# SzineszFeny_V11.net
KiCad netlist of a schematic drawn in EAGLE
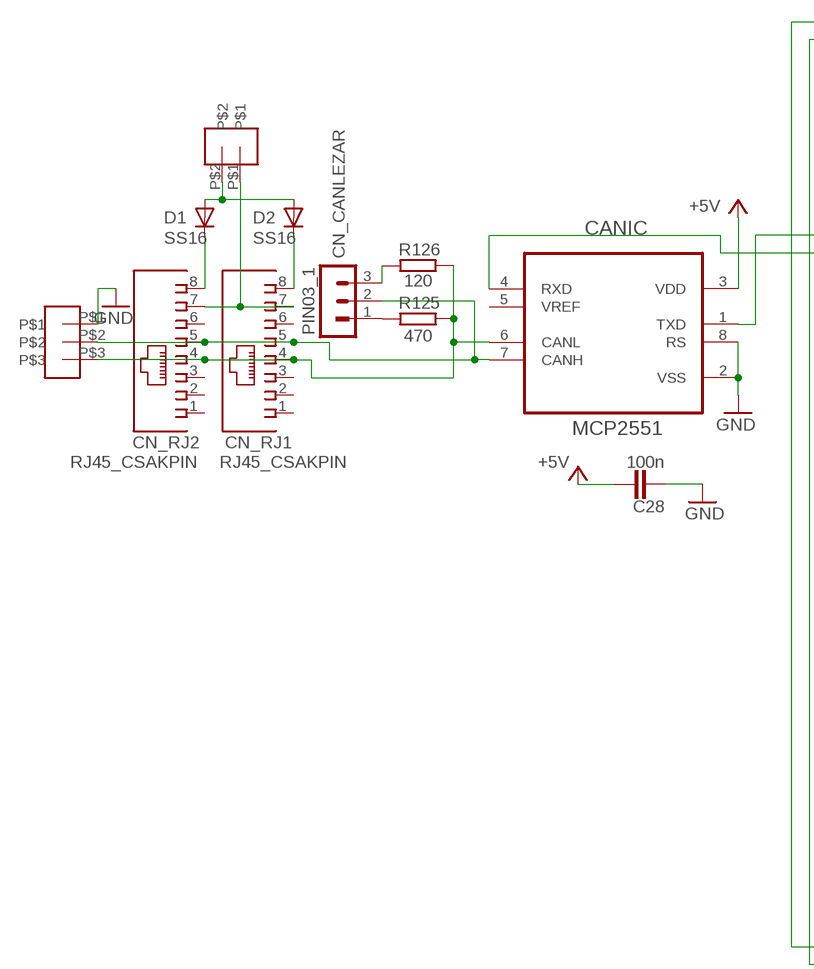
[diagram p0: schematic, sheet 1, part 1 of 2]
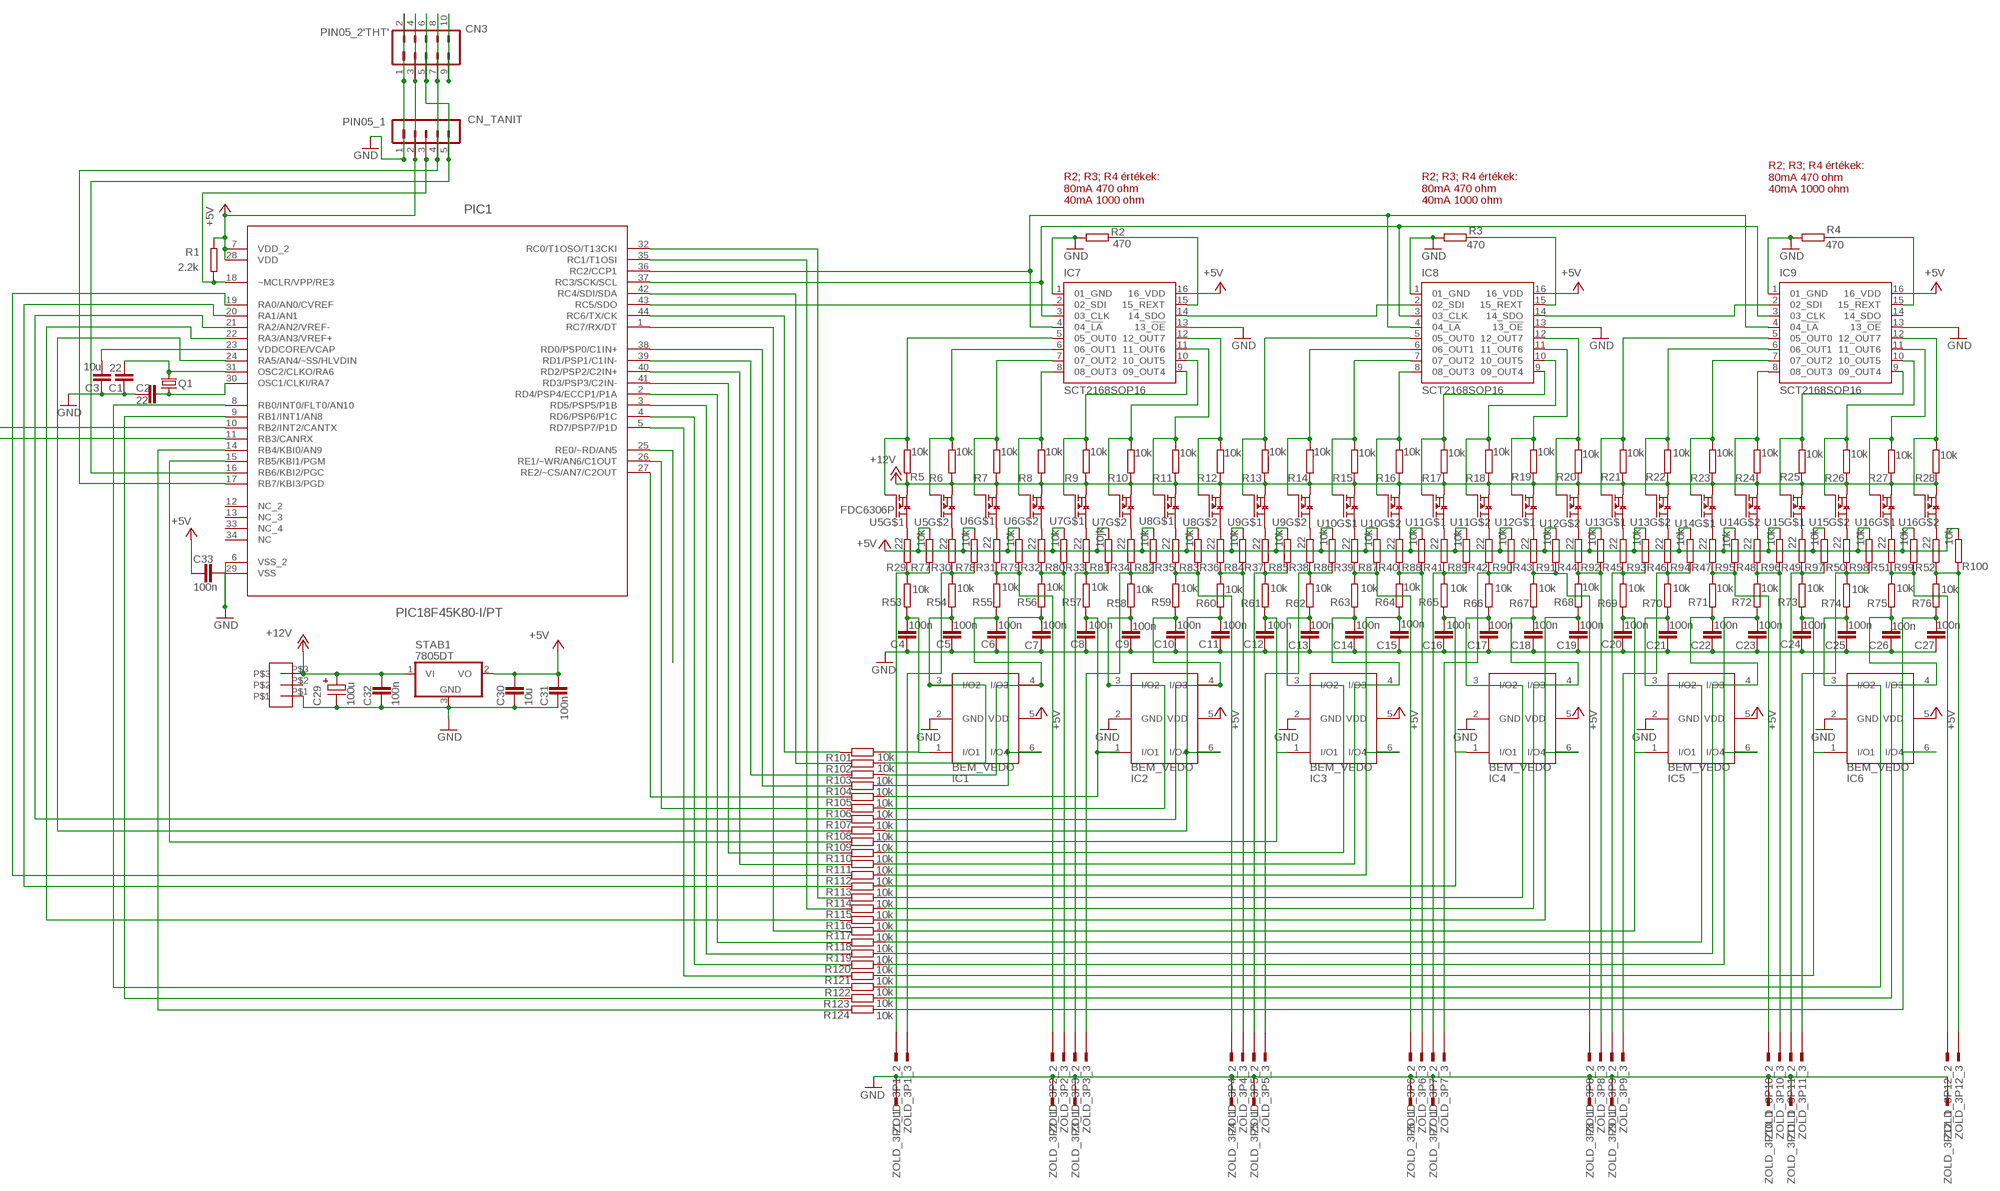
[diagram p1: schematic, sheet 1, part 2 of 2]

(export (version "E")
  (design (tool "Eeschema 10.0.6"))
  (components
    (comp (ref "C1")
      (value "22")
      (footprint "eagle-import:R0805")
      (libsource (lib "eagle-import") (part "C0805"))
    )
    (comp (ref "C2")
      (value "22")
      (footprint "eagle-import:R0805")
      (libsource (lib "eagle-import") (part "C0805"))
    )
    (comp (ref "C3")
      (value "10u")
      (footprint "eagle-import:R0805")
      (libsource (lib "eagle-import") (part "C0805"))
    )
    (comp (ref "C4")
      (value "100n")
      (footprint "eagle-import:R0805")
      (libsource (lib "eagle-import") (part "C0805"))
    )
    (comp (ref "C5")
      (value "100n")
      (footprint "eagle-import:R0805")
      (libsource (lib "eagle-import") (part "C0805"))
    )
    (comp (ref "C6")
      (value "100n")
      (footprint "eagle-import:R0805")
      (libsource (lib "eagle-import") (part "C0805"))
    )
    (comp (ref "C7")
      (value "100n")
      (footprint "eagle-import:R0805")
      (libsource (lib "eagle-import") (part "C0805"))
    )
    (comp (ref "C8")
      (value "100n")
      (footprint "eagle-import:R0805")
      (libsource (lib "eagle-import") (part "C0805"))
    )
    (comp (ref "C9")
      (value "100n")
      (footprint "eagle-import:R0805")
      (libsource (lib "eagle-import") (part "C0805"))
    )
    (comp (ref "C10")
      (value "100n")
      (footprint "eagle-import:R0805")
      (libsource (lib "eagle-import") (part "C0805"))
    )
    (comp (ref "C11")
      (value "100n")
      (footprint "eagle-import:R0805")
      (libsource (lib "eagle-import") (part "C0805"))
    )
    (comp (ref "C12")
      (value "100n")
      (footprint "eagle-import:R0805")
      (libsource (lib "eagle-import") (part "C0805"))
    )
    (comp (ref "C13")
      (value "100n")
      (footprint "eagle-import:R0805")
      (libsource (lib "eagle-import") (part "C0805"))
    )
    (comp (ref "C14")
      (value "100n")
      (footprint "eagle-import:R0805")
      (libsource (lib "eagle-import") (part "C0805"))
    )
    (comp (ref "C15")
      (value "100n")
      (footprint "eagle-import:R0805")
      (libsource (lib "eagle-import") (part "C0805"))
    )
    (comp (ref "C16")
      (value "100n")
      (footprint "eagle-import:R0805")
      (libsource (lib "eagle-import") (part "C0805"))
    )
    (comp (ref "C17")
      (value "100n")
      (footprint "eagle-import:R0805")
      (libsource (lib "eagle-import") (part "C0805"))
    )
    (comp (ref "C18")
      (value "100n")
      (footprint "eagle-import:R0805")
      (libsource (lib "eagle-import") (part "C0805"))
    )
    (comp (ref "C19")
      (value "100n")
      (footprint "eagle-import:R0805")
      (libsource (lib "eagle-import") (part "C0805"))
    )
    (comp (ref "C20")
      (value "100n")
      (footprint "eagle-import:R0805")
      (libsource (lib "eagle-import") (part "C0805"))
    )
    (comp (ref "C21")
      (value "100n")
      (footprint "eagle-import:R0805")
      (libsource (lib "eagle-import") (part "C0805"))
    )
    (comp (ref "C22")
      (value "100n")
      (footprint "eagle-import:R0805")
      (libsource (lib "eagle-import") (part "C0805"))
    )
    (comp (ref "C23")
      (value "100n")
      (footprint "eagle-import:R0805")
      (libsource (lib "eagle-import") (part "C0805"))
    )
    (comp (ref "C24")
      (value "100n")
      (footprint "eagle-import:R0805")
      (libsource (lib "eagle-import") (part "C0805"))
    )
    (comp (ref "C25")
      (value "100n")
      (footprint "eagle-import:R0805")
      (libsource (lib "eagle-import") (part "C0805"))
    )
    (comp (ref "C26")
      (value "100n")
      (footprint "eagle-import:R0805")
      (libsource (lib "eagle-import") (part "C0805"))
    )
    (comp (ref "C27")
      (value "100n")
      (footprint "eagle-import:R0805")
      (libsource (lib "eagle-import") (part "C0805"))
    )
    (comp (ref "C28")
      (value "100n")
      (footprint "eagle-import:R0805")
      (libsource (lib "eagle-import") (part "C0805"))
    )
    (comp (ref "C29")
      (value "100u")
      (footprint "eagle-import:C_EL1RASZT07")
      (libsource (lib "eagle-import") (part "C_EL1R07"))
    )
    (comp (ref "C30")
      (value "10u")
      (footprint "eagle-import:R0805")
      (libsource (lib "eagle-import") (part "C0805"))
    )
    (comp (ref "C31")
      (value "100n")
      (footprint "eagle-import:R0805")
      (libsource (lib "eagle-import") (part "C0805"))
    )
    (comp (ref "C32")
      (value "100n")
      (footprint "eagle-import:R0805")
      (libsource (lib "eagle-import") (part "C0805"))
    )
    (comp (ref "C33")
      (value "100n")
      (footprint "eagle-import:R0805")
      (libsource (lib "eagle-import") (part "C0805"))
    )
    (comp (ref "CANIC")
      (value "MCP2551")
      (footprint "eagle-import:DIP254P762X432-8")
      (fields (field (name "MPN") "MCP2551-I/P"))
      (libsource (lib "eagle-import") (part "MCP2551-I/P"))
    )
    (comp (ref "CN3")
      (value "PIN05_2'THT'")
      (footprint "eagle-import:PIN05_2")
      (libsource (lib "eagle-import") (part "PIN05_2'THT'"))
    )
    (comp (ref "CN_CANLEZAR")
      (value "PIN03_1")
      (footprint "eagle-import:PIN03_1")
      (libsource (lib "eagle-import") (part "PIN03_1"))
    )
    (comp (ref "CN_RJ1")
      (value "RJ45_CSAKPIN")
      (footprint "eagle-import:RJ45_CSAKPIN")
      (libsource (lib "eagle-import") (part "RJ45_CSAKPIN"))
    )
    (comp (ref "CN_RJ2")
      (value "RJ45_CSAKPIN")
      (footprint "eagle-import:RJ45_CSAKPIN")
      (libsource (lib "eagle-import") (part "RJ45_CSAKPIN"))
    )
    (comp (ref "CN_TANIT")
      (value "PIN05_1")
      (footprint "eagle-import:PIN05_1")
      (libsource (lib "eagle-import") (part "PIN05_1"))
    )
    (comp (ref "D1")
      (value "SS16")
      (footprint "eagle-import:DO214AC")
      (fields (field (name "D1") "SS16"))
      (libsource (lib "eagle-import") (part "DDO214AC"))
    )
    (comp (ref "D2")
      (value "SS16")
      (footprint "eagle-import:DO214AC")
      (fields (field (name "D2") "SS16"))
      (libsource (lib "eagle-import") (part "DDO214AC"))
    )
    (comp (ref "IC1")
      (value "BEM_VEDO")
      (footprint "eagle-import:TSOP-6")
      (libsource (lib "eagle-import") (part "BEM_VEDO"))
    )
    (comp (ref "IC2")
      (value "BEM_VEDO")
      (footprint "eagle-import:TSOP-6")
      (libsource (lib "eagle-import") (part "BEM_VEDO"))
    )
    (comp (ref "IC3")
      (value "BEM_VEDO")
      (footprint "eagle-import:TSOP-6")
      (libsource (lib "eagle-import") (part "BEM_VEDO"))
    )
    (comp (ref "IC4")
      (value "BEM_VEDO")
      (footprint "eagle-import:TSOP-6")
      (libsource (lib "eagle-import") (part "BEM_VEDO"))
    )
    (comp (ref "IC5")
      (value "BEM_VEDO")
      (footprint "eagle-import:TSOP-6")
      (libsource (lib "eagle-import") (part "BEM_VEDO"))
    )
    (comp (ref "IC6")
      (value "BEM_VEDO")
      (footprint "eagle-import:TSOP-6")
      (libsource (lib "eagle-import") (part "BEM_VEDO"))
    )
    (comp (ref "IC7")
      (value "SCT2168SOP16")
      (footprint "eagle-import:SO16")
      (libsource (lib "eagle-import") (part "SCT2168SOP16"))
    )
    (comp (ref "IC8")
      (value "SCT2168SOP16")
      (footprint "eagle-import:SO16")
      (libsource (lib "eagle-import") (part "SCT2168SOP16"))
    )
    (comp (ref "IC9")
      (value "SCT2168SOP16")
      (footprint "eagle-import:SO16")
      (libsource (lib "eagle-import") (part "SCT2168SOP16"))
    )
    (comp (ref "PIC1")
      (value "PIC18F45K80-I/PT")
      (footprint "eagle-import:QFP80P1200X1200X120-44N")
      (fields (field (name "MPN") "PIC18F4580-I/PT"))
      (libsource (lib "eagle-import") (part "PIC18F45K80-I/PT"))
    )
    (comp (ref "Q1")
      (value "XTAL_2QS")
      (footprint "eagle-import:XTAL_QS")
      (libsource (lib "eagle-import") (part "XTAL_2QS"))
    )
    (comp (ref "R1")
      (value "2.2k")
      (footprint "eagle-import:R0805@1")
      (libsource (lib "eagle-import") (part "R_EU0805"))
    )
    (comp (ref "R2")
      (value "470")
      (footprint "eagle-import:R0805@1")
      (libsource (lib "eagle-import") (part "R_EU0805"))
    )
    (comp (ref "R3")
      (value "470")
      (footprint "eagle-import:R0805@1")
      (libsource (lib "eagle-import") (part "R_EU0805"))
    )
    (comp (ref "R4")
      (value "470")
      (footprint "eagle-import:R0805@1")
      (libsource (lib "eagle-import") (part "R_EU0805"))
    )
    (comp (ref "R5")
      (value "10k")
      (footprint "eagle-import:R0805@1")
      (libsource (lib "eagle-import") (part "R_EU0805"))
    )
    (comp (ref "R6")
      (value "10k")
      (footprint "eagle-import:R0805@1")
      (libsource (lib "eagle-import") (part "R_EU0805"))
    )
    (comp (ref "R7")
      (value "10k")
      (footprint "eagle-import:R0805@1")
      (libsource (lib "eagle-import") (part "R_EU0805"))
    )
    (comp (ref "R8")
      (value "10k")
      (footprint "eagle-import:R0805@1")
      (libsource (lib "eagle-import") (part "R_EU0805"))
    )
    (comp (ref "R9")
      (value "10k")
      (footprint "eagle-import:R0805@1")
      (libsource (lib "eagle-import") (part "R_EU0805"))
    )
    (comp (ref "R10")
      (value "10k")
      (footprint "eagle-import:R0805@1")
      (libsource (lib "eagle-import") (part "R_EU0805"))
    )
    (comp (ref "R11")
      (value "10k")
      (footprint "eagle-import:R0805@1")
      (libsource (lib "eagle-import") (part "R_EU0805"))
    )
    (comp (ref "R12")
      (value "10k")
      (footprint "eagle-import:R0805@1")
      (libsource (lib "eagle-import") (part "R_EU0805"))
    )
    (comp (ref "R13")
      (value "10k")
      (footprint "eagle-import:R0805@1")
      (libsource (lib "eagle-import") (part "R_EU0805"))
    )
    (comp (ref "R14")
      (value "10k")
      (footprint "eagle-import:R0805@1")
      (libsource (lib "eagle-import") (part "R_EU0805"))
    )
    (comp (ref "R15")
      (value "10k")
      (footprint "eagle-import:R0805@1")
      (libsource (lib "eagle-import") (part "R_EU0805"))
    )
    (comp (ref "R16")
      (value "10k")
      (footprint "eagle-import:R0805@1")
      (libsource (lib "eagle-import") (part "R_EU0805"))
    )
    (comp (ref "R17")
      (value "10k")
      (footprint "eagle-import:R0805@1")
      (libsource (lib "eagle-import") (part "R_EU0805"))
    )
    (comp (ref "R18")
      (value "10k")
      (footprint "eagle-import:R0805@1")
      (libsource (lib "eagle-import") (part "R_EU0805"))
    )
    (comp (ref "R19")
      (value "10k")
      (footprint "eagle-import:R0805@1")
      (libsource (lib "eagle-import") (part "R_EU0805"))
    )
    (comp (ref "R20")
      (value "10k")
      (footprint "eagle-import:R0805@1")
      (libsource (lib "eagle-import") (part "R_EU0805"))
    )
    (comp (ref "R21")
      (value "10k")
      (footprint "eagle-import:R0805@1")
      (libsource (lib "eagle-import") (part "R_EU0805"))
    )
    (comp (ref "R22")
      (value "10k")
      (footprint "eagle-import:R0805@1")
      (libsource (lib "eagle-import") (part "R_EU0805"))
    )
    (comp (ref "R23")
      (value "10k")
      (footprint "eagle-import:R0805@1")
      (libsource (lib "eagle-import") (part "R_EU0805"))
    )
    (comp (ref "R24")
      (value "10k")
      (footprint "eagle-import:R0805@1")
      (libsource (lib "eagle-import") (part "R_EU0805"))
    )
    (comp (ref "R25")
      (value "10k")
      (footprint "eagle-import:R0805@1")
      (libsource (lib "eagle-import") (part "R_EU0805"))
    )
    (comp (ref "R26")
      (value "10k")
      (footprint "eagle-import:R0805@1")
      (libsource (lib "eagle-import") (part "R_EU0805"))
    )
    (comp (ref "R27")
      (value "10k")
      (footprint "eagle-import:R0805@1")
      (libsource (lib "eagle-import") (part "R_EU0805"))
    )
    (comp (ref "R28")
      (value "10k")
      (footprint "eagle-import:R0805@1")
      (libsource (lib "eagle-import") (part "R_EU0805"))
    )
    (comp (ref "R29")
      (value "22")
      (footprint "eagle-import:R0805@1")
      (libsource (lib "eagle-import") (part "R_EU0805"))
    )
    (comp (ref "R30")
      (value "22")
      (footprint "eagle-import:R0805@1")
      (libsource (lib "eagle-import") (part "R_EU0805"))
    )
    (comp (ref "R31")
      (value "22")
      (footprint "eagle-import:R0805@1")
      (libsource (lib "eagle-import") (part "R_EU0805"))
    )
    (comp (ref "R32")
      (value "22")
      (footprint "eagle-import:R0805@1")
      (libsource (lib "eagle-import") (part "R_EU0805"))
    )
    (comp (ref "R33")
      (value "22")
      (footprint "eagle-import:R0805@1")
      (libsource (lib "eagle-import") (part "R_EU0805"))
    )
    (comp (ref "R34")
      (value "22")
      (footprint "eagle-import:R0805@1")
      (libsource (lib "eagle-import") (part "R_EU0805"))
    )
    (comp (ref "R35")
      (value "22")
      (footprint "eagle-import:R0805@1")
      (libsource (lib "eagle-import") (part "R_EU0805"))
    )
    (comp (ref "R36")
      (value "22")
      (footprint "eagle-import:R0805@1")
      (libsource (lib "eagle-import") (part "R_EU0805"))
    )
    (comp (ref "R37")
      (value "22")
      (footprint "eagle-import:R0805@1")
      (libsource (lib "eagle-import") (part "R_EU0805"))
    )
    (comp (ref "R38")
      (value "22")
      (footprint "eagle-import:R0805@1")
      (libsource (lib "eagle-import") (part "R_EU0805"))
    )
    (comp (ref "R39")
      (value "22")
      (footprint "eagle-import:R0805@1")
      (libsource (lib "eagle-import") (part "R_EU0805"))
    )
    (comp (ref "R40")
      (value "22")
      (footprint "eagle-import:R0805@1")
      (libsource (lib "eagle-import") (part "R_EU0805"))
    )
    (comp (ref "R41")
      (value "22")
      (footprint "eagle-import:R0805@1")
      (libsource (lib "eagle-import") (part "R_EU0805"))
    )
    (comp (ref "R42")
      (value "22")
      (footprint "eagle-import:R0805@1")
      (libsource (lib "eagle-import") (part "R_EU0805"))
    )
    (comp (ref "R43")
      (value "22")
      (footprint "eagle-import:R0805@1")
      (libsource (lib "eagle-import") (part "R_EU0805"))
    )
    (comp (ref "R44")
      (value "22")
      (footprint "eagle-import:R0805@1")
      (libsource (lib "eagle-import") (part "R_EU0805"))
    )
    (comp (ref "R45")
      (value "22")
      (footprint "eagle-import:R0805@1")
      (libsource (lib "eagle-import") (part "R_EU0805"))
    )
    (comp (ref "R46")
      (value "22")
      (footprint "eagle-import:R0805@1")
      (libsource (lib "eagle-import") (part "R_EU0805"))
    )
    (comp (ref "R47")
      (value "22")
      (footprint "eagle-import:R0805@1")
      (libsource (lib "eagle-import") (part "R_EU0805"))
    )
    (comp (ref "R48")
      (value "22")
      (footprint "eagle-import:R0805@1")
      (libsource (lib "eagle-import") (part "R_EU0805"))
    )
    (comp (ref "R49")
      (value "22")
      (footprint "eagle-import:R0805@1")
      (libsource (lib "eagle-import") (part "R_EU0805"))
    )
    (comp (ref "R50")
      (value "22")
      (footprint "eagle-import:R0805@1")
      (libsource (lib "eagle-import") (part "R_EU0805"))
    )
    (comp (ref "R51")
      (value "22")
      (footprint "eagle-import:R0805@1")
      (libsource (lib "eagle-import") (part "R_EU0805"))
    )
    (comp (ref "R52")
      (value "22")
      (footprint "eagle-import:R0805@1")
      (libsource (lib "eagle-import") (part "R_EU0805"))
    )
    (comp (ref "R53")
      (value "10k")
      (footprint "eagle-import:R0805@1")
      (libsource (lib "eagle-import") (part "R_EU0805"))
    )
    (comp (ref "R54")
      (value "10k")
      (footprint "eagle-import:R0805@1")
      (libsource (lib "eagle-import") (part "R_EU0805"))
    )
    (comp (ref "R55")
      (value "10k")
      (footprint "eagle-import:R0805@1")
      (libsource (lib "eagle-import") (part "R_EU0805"))
    )
    (comp (ref "R56")
      (value "10k")
      (footprint "eagle-import:R0805@1")
      (libsource (lib "eagle-import") (part "R_EU0805"))
    )
    (comp (ref "R57")
      (value "10k")
      (footprint "eagle-import:R0805@1")
      (libsource (lib "eagle-import") (part "R_EU0805"))
    )
    (comp (ref "R58")
      (value "10k")
      (footprint "eagle-import:R0805@1")
      (libsource (lib "eagle-import") (part "R_EU0805"))
    )
    (comp (ref "R59")
      (value "10k")
      (footprint "eagle-import:R0805@1")
      (libsource (lib "eagle-import") (part "R_EU0805"))
    )
    (comp (ref "R60")
      (value "10k")
      (footprint "eagle-import:R0805@1")
      (libsource (lib "eagle-import") (part "R_EU0805"))
    )
    (comp (ref "R61")
      (value "10k")
      (footprint "eagle-import:R0805@1")
      (libsource (lib "eagle-import") (part "R_EU0805"))
    )
    (comp (ref "R62")
      (value "10k")
      (footprint "eagle-import:R0805@1")
      (libsource (lib "eagle-import") (part "R_EU0805"))
    )
    (comp (ref "R63")
      (value "10k")
      (footprint "eagle-import:R0805@1")
      (libsource (lib "eagle-import") (part "R_EU0805"))
    )
    (comp (ref "R64")
      (value "10k")
      (footprint "eagle-import:R0805@1")
      (libsource (lib "eagle-import") (part "R_EU0805"))
    )
    (comp (ref "R65")
      (value "10k")
      (footprint "eagle-import:R0805@1")
      (libsource (lib "eagle-import") (part "R_EU0805"))
    )
    (comp (ref "R66")
      (value "10k")
      (footprint "eagle-import:R0805@1")
      (libsource (lib "eagle-import") (part "R_EU0805"))
    )
    (comp (ref "R67")
      (value "10k")
      (footprint "eagle-import:R0805@1")
      (libsource (lib "eagle-import") (part "R_EU0805"))
    )
    (comp (ref "R68")
      (value "10k")
      (footprint "eagle-import:R0805@1")
      (libsource (lib "eagle-import") (part "R_EU0805"))
    )
    (comp (ref "R69")
      (value "10k")
      (footprint "eagle-import:R0805@1")
      (libsource (lib "eagle-import") (part "R_EU0805"))
    )
    (comp (ref "R70")
      (value "10k")
      (footprint "eagle-import:R0805@1")
      (libsource (lib "eagle-import") (part "R_EU0805"))
    )
    (comp (ref "R71")
      (value "10k")
      (footprint "eagle-import:R0805@1")
      (libsource (lib "eagle-import") (part "R_EU0805"))
    )
    (comp (ref "R72")
      (value "10k")
      (footprint "eagle-import:R0805@1")
      (libsource (lib "eagle-import") (part "R_EU0805"))
    )
    (comp (ref "R73")
      (value "10k")
      (footprint "eagle-import:R0805@1")
      (libsource (lib "eagle-import") (part "R_EU0805"))
    )
    (comp (ref "R74")
      (value "10k")
      (footprint "eagle-import:R0805@1")
      (libsource (lib "eagle-import") (part "R_EU0805"))
    )
    (comp (ref "R75")
      (value "10k")
      (footprint "eagle-import:R0805@1")
      (libsource (lib "eagle-import") (part "R_EU0805"))
    )
    (comp (ref "R76")
      (value "10k")
      (footprint "eagle-import:R0805@1")
      (libsource (lib "eagle-import") (part "R_EU0805"))
    )
    (comp (ref "R77")
      (value "10k")
      (footprint "eagle-import:R0805@1")
      (libsource (lib "eagle-import") (part "R_EU0805"))
    )
    (comp (ref "R78")
      (value "10k")
      (footprint "eagle-import:R0805@1")
      (libsource (lib "eagle-import") (part "R_EU0805"))
    )
    (comp (ref "R79")
      (value "10k")
      (footprint "eagle-import:R0805@1")
      (libsource (lib "eagle-import") (part "R_EU0805"))
    )
    (comp (ref "R80")
      (value "10k")
      (footprint "eagle-import:R0805@1")
      (libsource (lib "eagle-import") (part "R_EU0805"))
    )
    (comp (ref "R81")
      (value "10jk")
      (footprint "eagle-import:R0805@1")
      (libsource (lib "eagle-import") (part "R_EU0805"))
    )
    (comp (ref "R82")
      (value "10k")
      (footprint "eagle-import:R0805@1")
      (libsource (lib "eagle-import") (part "R_EU0805"))
    )
    (comp (ref "R83")
      (value "10k")
      (footprint "eagle-import:R0805@1")
      (libsource (lib "eagle-import") (part "R_EU0805"))
    )
    (comp (ref "R84")
      (value "10k")
      (footprint "eagle-import:R0805@1")
      (libsource (lib "eagle-import") (part "R_EU0805"))
    )
    (comp (ref "R85")
      (value "10k")
      (footprint "eagle-import:R0805@1")
      (libsource (lib "eagle-import") (part "R_EU0805"))
    )
    (comp (ref "R86")
      (value "10k")
      (footprint "eagle-import:R0805@1")
      (libsource (lib "eagle-import") (part "R_EU0805"))
    )
    (comp (ref "R87")
      (value "10k")
      (footprint "eagle-import:R0805@1")
      (libsource (lib "eagle-import") (part "R_EU0805"))
    )
    (comp (ref "R88")
      (value "10k")
      (footprint "eagle-import:R0805@1")
      (libsource (lib "eagle-import") (part "R_EU0805"))
    )
    (comp (ref "R89")
      (value "10k")
      (footprint "eagle-import:R0805@1")
      (libsource (lib "eagle-import") (part "R_EU0805"))
    )
    (comp (ref "R90")
      (value "10k")
      (footprint "eagle-import:R0805@1")
      (libsource (lib "eagle-import") (part "R_EU0805"))
    )
    (comp (ref "R91")
      (value "10k")
      (footprint "eagle-import:R0805@1")
      (libsource (lib "eagle-import") (part "R_EU0805"))
    )
    (comp (ref "R92")
      (value "10k")
      (footprint "eagle-import:R0805@1")
      (libsource (lib "eagle-import") (part "R_EU0805"))
    )
    (comp (ref "R93")
      (value "10k")
      (footprint "eagle-import:R0805@1")
      (libsource (lib "eagle-import") (part "R_EU0805"))
    )
    (comp (ref "R94")
      (value "10k")
      (footprint "eagle-import:R0805@1")
      (libsource (lib "eagle-import") (part "R_EU0805"))
    )
    (comp (ref "R95")
      (value "10k")
      (footprint "eagle-import:R0805@1")
      (libsource (lib "eagle-import") (part "R_EU0805"))
    )
    (comp (ref "R96")
      (value "10k")
      (footprint "eagle-import:R0805@1")
      (libsource (lib "eagle-import") (part "R_EU0805"))
    )
    (comp (ref "R97")
      (value "10k")
      (footprint "eagle-import:R0805@1")
      (libsource (lib "eagle-import") (part "R_EU0805"))
    )
    (comp (ref "R98")
      (value "10k")
      (footprint "eagle-import:R0805@1")
      (libsource (lib "eagle-import") (part "R_EU0805"))
    )
    (comp (ref "R99")
      (value "10k")
      (footprint "eagle-import:R0805@1")
      (libsource (lib "eagle-import") (part "R_EU0805"))
    )
    (comp (ref "R100")
      (value "10k")
      (footprint "eagle-import:R0805@1")
      (libsource (lib "eagle-import") (part "R_EU0805"))
    )
    (comp (ref "R101")
      (value "10k")
      (footprint "eagle-import:R0805@1")
      (libsource (lib "eagle-import") (part "R_EU0805"))
    )
    (comp (ref "R102")
      (value "10k")
      (footprint "eagle-import:R0805@1")
      (libsource (lib "eagle-import") (part "R_EU0805"))
    )
    (comp (ref "R103")
      (value "10k")
      (footprint "eagle-import:R0805@1")
      (libsource (lib "eagle-import") (part "R_EU0805"))
    )
    (comp (ref "R104")
      (value "10k")
      (footprint "eagle-import:R0805@1")
      (libsource (lib "eagle-import") (part "R_EU0805"))
    )
    (comp (ref "R105")
      (value "10k")
      (footprint "eagle-import:R0805@1")
      (libsource (lib "eagle-import") (part "R_EU0805"))
    )
    (comp (ref "R106")
      (value "10k")
      (footprint "eagle-import:R0805@1")
      (libsource (lib "eagle-import") (part "R_EU0805"))
    )
    (comp (ref "R107")
      (value "10k")
      (footprint "eagle-import:R0805@1")
      (libsource (lib "eagle-import") (part "R_EU0805"))
    )
    (comp (ref "R108")
      (value "10k")
      (footprint "eagle-import:R0805@1")
      (libsource (lib "eagle-import") (part "R_EU0805"))
    )
    (comp (ref "R109")
      (value "10k")
      (footprint "eagle-import:R0805@1")
      (libsource (lib "eagle-import") (part "R_EU0805"))
    )
    (comp (ref "R110")
      (value "10k")
      (footprint "eagle-import:R0805@1")
      (libsource (lib "eagle-import") (part "R_EU0805"))
    )
    (comp (ref "R111")
      (value "10k")
      (footprint "eagle-import:R0805@1")
      (libsource (lib "eagle-import") (part "R_EU0805"))
    )
    (comp (ref "R112")
      (value "10k")
      (footprint "eagle-import:R0805@1")
      (libsource (lib "eagle-import") (part "R_EU0805"))
    )
    (comp (ref "R113")
      (value "10k")
      (footprint "eagle-import:R0805@1")
      (libsource (lib "eagle-import") (part "R_EU0805"))
    )
    (comp (ref "R114")
      (value "10k")
      (footprint "eagle-import:R0805@1")
      (libsource (lib "eagle-import") (part "R_EU0805"))
    )
    (comp (ref "R115")
      (value "10k")
      (footprint "eagle-import:R0805@1")
      (libsource (lib "eagle-import") (part "R_EU0805"))
    )
    (comp (ref "R116")
      (value "10k")
      (footprint "eagle-import:R0805@1")
      (libsource (lib "eagle-import") (part "R_EU0805"))
    )
    (comp (ref "R117")
      (value "10k")
      (footprint "eagle-import:R0805@1")
      (libsource (lib "eagle-import") (part "R_EU0805"))
    )
    (comp (ref "R118")
      (value "10k")
      (footprint "eagle-import:R0805@1")
      (libsource (lib "eagle-import") (part "R_EU0805"))
    )
    (comp (ref "R119")
      (value "10k")
      (footprint "eagle-import:R0805@1")
      (libsource (lib "eagle-import") (part "R_EU0805"))
    )
    (comp (ref "R120")
      (value "10k")
      (footprint "eagle-import:R0805@1")
      (libsource (lib "eagle-import") (part "R_EU0805"))
    )
    (comp (ref "R121")
      (value "10k")
      (footprint "eagle-import:R0805@1")
      (libsource (lib "eagle-import") (part "R_EU0805"))
    )
    (comp (ref "R122")
      (value "10k")
      (footprint "eagle-import:R0805@1")
      (libsource (lib "eagle-import") (part "R_EU0805"))
    )
    (comp (ref "R123")
      (value "10k")
      (footprint "eagle-import:R0805@1")
      (libsource (lib "eagle-import") (part "R_EU0805"))
    )
    (comp (ref "R124")
      (value "10k")
      (footprint "eagle-import:R0805@1")
      (libsource (lib "eagle-import") (part "R_EU0805"))
    )
    (comp (ref "R125")
      (value "470")
      (footprint "eagle-import:R0805@1")
      (libsource (lib "eagle-import") (part "R_EU0805"))
    )
    (comp (ref "R126")
      (value "120")
      (footprint "eagle-import:R0805@1")
      (libsource (lib "eagle-import") (part "R_EU0805"))
    )
    (comp (ref "STAB1")
      (value "7805DT")
      (footprint "eagle-import:TO252")
      (libsource (lib "eagle-import") (part "78DT05"))
    )
    (comp (ref "U$1")
      (value "FEHER_TUS_3")
      (footprint "eagle-import:FEHER_TUS_3")
      (libsource (lib "eagle-import") (part "FEHER_TUS_3"))
    )
    (comp (ref "U$20")
      (value "FEHER_TUS_3")
      (footprint "eagle-import:FEHER_TUS_3")
      (libsource (lib "eagle-import") (part "FEHER_TUS_3"))
    )
    (comp (ref "U$21")
      (value "FEHER_TUS_2ALLO")
      (footprint "eagle-import:FEHER_TUS_2")
      (libsource (lib "eagle-import") (part "FEHER_TUS_2ALLO"))
    )
    (comp (ref "U5")
      (value "FDC6306P")
      (footprint "eagle-import:SOT26")
      (libsource (lib "eagle-import") (part "AP2625GY-HF-3SOT26"))
    )
    (comp (ref "U6")
      (value "AP2625GY-HF-3SOT26")
      (footprint "eagle-import:SOT26")
      (libsource (lib "eagle-import") (part "AP2625GY-HF-3SOT26"))
    )
    (comp (ref "U7")
      (value "AP2625GY-HF-3SOT26")
      (footprint "eagle-import:SOT26")
      (libsource (lib "eagle-import") (part "AP2625GY-HF-3SOT26"))
    )
    (comp (ref "U8")
      (value "AP2625GY-HF-3SOT26")
      (footprint "eagle-import:SOT26")
      (libsource (lib "eagle-import") (part "AP2625GY-HF-3SOT26"))
    )
    (comp (ref "U9")
      (value "AP2625GY-HF-3SOT26")
      (footprint "eagle-import:SOT26")
      (libsource (lib "eagle-import") (part "AP2625GY-HF-3SOT26"))
    )
    (comp (ref "U10")
      (value "AP2625GY-HF-3SOT26")
      (footprint "eagle-import:SOT26")
      (libsource (lib "eagle-import") (part "AP2625GY-HF-3SOT26"))
    )
    (comp (ref "U11")
      (value "AP2625GY-HF-3SOT26")
      (footprint "eagle-import:SOT26")
      (libsource (lib "eagle-import") (part "AP2625GY-HF-3SOT26"))
    )
    (comp (ref "U12")
      (value "AP2625GY-HF-3SOT26")
      (footprint "eagle-import:SOT26")
      (libsource (lib "eagle-import") (part "AP2625GY-HF-3SOT26"))
    )
    (comp (ref "U13")
      (value "AP2625GY-HF-3SOT26")
      (footprint "eagle-import:SOT26")
      (libsource (lib "eagle-import") (part "AP2625GY-HF-3SOT26"))
    )
    (comp (ref "U14")
      (value "AP2625GY-HF-3SOT26")
      (footprint "eagle-import:SOT26")
      (libsource (lib "eagle-import") (part "AP2625GY-HF-3SOT26"))
    )
    (comp (ref "U15")
      (value "AP2625GY-HF-3SOT26")
      (footprint "eagle-import:SOT26")
      (libsource (lib "eagle-import") (part "AP2625GY-HF-3SOT26"))
    )
    (comp (ref "U16")
      (value "FDC6306P")
      (footprint "eagle-import:SOT26")
      (libsource (lib "eagle-import") (part "AP2625GY-HF-3SOT26"))
    )
    (comp (ref "ZOLD_3P1")
      (value "ZOLD_KICSI_3P")
      (footprint "eagle-import:ZOLD_KICSI_3P")
      (libsource (lib "eagle-import") (part "ZOLD_KICSI_3P"))
    )
    (comp (ref "ZOLD_3P2")
      (value "ZOLD_KICSI_3P")
      (footprint "eagle-import:ZOLD_KICSI_3P")
      (libsource (lib "eagle-import") (part "ZOLD_KICSI_3P"))
    )
    (comp (ref "ZOLD_3P3")
      (value "ZOLD_KICSI_3P")
      (footprint "eagle-import:ZOLD_KICSI_3P")
      (libsource (lib "eagle-import") (part "ZOLD_KICSI_3P"))
    )
    (comp (ref "ZOLD_3P4")
      (value "ZOLD_KICSI_3P")
      (footprint "eagle-import:ZOLD_KICSI_3P")
      (libsource (lib "eagle-import") (part "ZOLD_KICSI_3P"))
    )
    (comp (ref "ZOLD_3P5")
      (value "ZOLD_KICSI_3P")
      (footprint "eagle-import:ZOLD_KICSI_3P")
      (libsource (lib "eagle-import") (part "ZOLD_KICSI_3P"))
    )
    (comp (ref "ZOLD_3P6")
      (value "ZOLD_KICSI_3P")
      (footprint "eagle-import:ZOLD_KICSI_3P")
      (libsource (lib "eagle-import") (part "ZOLD_KICSI_3P"))
    )
    (comp (ref "ZOLD_3P7")
      (value "ZOLD_KICSI_3P")
      (footprint "eagle-import:ZOLD_KICSI_3P")
      (libsource (lib "eagle-import") (part "ZOLD_KICSI_3P"))
    )
    (comp (ref "ZOLD_3P8")
      (value "ZOLD_KICSI_3P")
      (footprint "eagle-import:ZOLD_KICSI_3P")
      (libsource (lib "eagle-import") (part "ZOLD_KICSI_3P"))
    )
    (comp (ref "ZOLD_3P9")
      (value "ZOLD_KICSI_3P")
      (footprint "eagle-import:ZOLD_KICSI_3P")
      (libsource (lib "eagle-import") (part "ZOLD_KICSI_3P"))
    )
    (comp (ref "ZOLD_3P10")
      (value "ZOLD_KICSI_3P")
      (footprint "eagle-import:ZOLD_KICSI_3P")
      (libsource (lib "eagle-import") (part "ZOLD_KICSI_3P"))
    )
    (comp (ref "ZOLD_3P11")
      (value "ZOLD_KICSI_3P")
      (footprint "eagle-import:ZOLD_KICSI_3P")
      (libsource (lib "eagle-import") (part "ZOLD_KICSI_3P"))
    )
    (comp (ref "ZOLD_3P12")
      (value "ZOLD_KICSI_3P")
      (footprint "eagle-import:ZOLD_KICSI_3P")
      (libsource (lib "eagle-import") (part "ZOLD_KICSI_3P"))
    )
  )
  (nets
    (net (code "1") (name "+5V") (class "Default")
      (node (ref "C28") (pin "1") (pinfunction "1_1") (pintype "passive"))
      (node (ref "C30") (pin "1") (pinfunction "1_1") (pintype "passive"))
      (node (ref "C31") (pin "1") (pinfunction "1_1") (pintype "passive"))
      (node (ref "C33") (pin "2") (pinfunction "2_2") (pintype "passive"))
      (node (ref "CANIC") (pin "3") (pinfunction "VDD_3") (pintype "power_in"))
      (node (ref "CN3") (pin "3") (pinfunction "3_3") (pintype "passive"))
      (node (ref "CN3") (pin "4") (pinfunction "4_4") (pintype "passive"))
      (node (ref "CN_TANIT") (pin "2") (pinfunction "2_2") (pintype "passive"))
      (node (ref "IC1") (pin "5") (pinfunction "VDD_5") (pintype "bidirectional"))
      (node (ref "IC2") (pin "5") (pinfunction "VDD_5") (pintype "bidirectional"))
      (node (ref "IC3") (pin "5") (pinfunction "VDD_5") (pintype "bidirectional"))
      (node (ref "IC4") (pin "5") (pinfunction "VDD_5") (pintype "bidirectional"))
      (node (ref "IC5") (pin "5") (pinfunction "VDD_5") (pintype "bidirectional"))
      (node (ref "IC6") (pin "5") (pinfunction "VDD_5") (pintype "bidirectional"))
      (node (ref "IC7") (pin "16") (pinfunction "16_VDD_16") (pintype "power_in"))
      (node (ref "IC8") (pin "16") (pinfunction "16_VDD_16") (pintype "power_in"))
      (node (ref "IC9") (pin "16") (pinfunction "16_VDD_16") (pintype "power_in"))
      (node (ref "PIC1") (pin "28") (pinfunction "VDD_28") (pintype "power_in"))
      (node (ref "PIC1") (pin "7") (pinfunction "VDD_2_7") (pintype "power_in"))
      (node (ref "R1") (pin "2") (pinfunction "E_2") (pintype "passive"))
      (node (ref "R100") (pin "1") (pinfunction "A_1") (pintype "passive"))
      (node (ref "R77") (pin "1") (pinfunction "A_1") (pintype "passive"))
      (node (ref "R78") (pin "1") (pinfunction "A_1") (pintype "passive"))
      (node (ref "R79") (pin "1") (pinfunction "A_1") (pintype "passive"))
      (node (ref "R80") (pin "1") (pinfunction "A_1") (pintype "passive"))
      (node (ref "R81") (pin "1") (pinfunction "A_1") (pintype "passive"))
      (node (ref "R82") (pin "1") (pinfunction "A_1") (pintype "passive"))
      (node (ref "R83") (pin "1") (pinfunction "A_1") (pintype "passive"))
      (node (ref "R84") (pin "1") (pinfunction "A_1") (pintype "passive"))
      (node (ref "R85") (pin "1") (pinfunction "A_1") (pintype "passive"))
      (node (ref "R86") (pin "1") (pinfunction "A_1") (pintype "passive"))
      (node (ref "R87") (pin "1") (pinfunction "A_1") (pintype "passive"))
      (node (ref "R88") (pin "1") (pinfunction "A_1") (pintype "passive"))
      (node (ref "R89") (pin "1") (pinfunction "A_1") (pintype "passive"))
      (node (ref "R90") (pin "1") (pinfunction "A_1") (pintype "passive"))
      (node (ref "R91") (pin "1") (pinfunction "A_1") (pintype "passive"))
      (node (ref "R92") (pin "1") (pinfunction "A_1") (pintype "passive"))
      (node (ref "R93") (pin "1") (pinfunction "A_1") (pintype "passive"))
      (node (ref "R94") (pin "1") (pinfunction "A_1") (pintype "passive"))
      (node (ref "R95") (pin "1") (pinfunction "A_1") (pintype "passive"))
      (node (ref "R96") (pin "1") (pinfunction "A_1") (pintype "passive"))
      (node (ref "R97") (pin "1") (pinfunction "A_1") (pintype "passive"))
      (node (ref "R98") (pin "1") (pinfunction "A_1") (pintype "passive"))
      (node (ref "R99") (pin "1") (pinfunction "A_1") (pintype "passive"))
      (node (ref "STAB1") (pin "2") (pinfunction "VO_2") (pintype "passive"))
    )
    (net (code "2") (name "+12V") (class "Default")
      (node (ref "C29") (pin "P+") (pinfunction "P+_P+") (pintype "passive"))
      (node (ref "C32") (pin "1") (pinfunction "1_1") (pintype "passive"))
      (node (ref "R10") (pin "1") (pinfunction "A_1") (pintype "passive"))
      (node (ref "R11") (pin "1") (pinfunction "A_1") (pintype "passive"))
      (node (ref "R12") (pin "1") (pinfunction "A_1") (pintype "passive"))
      (node (ref "R13") (pin "1") (pinfunction "A_1") (pintype "passive"))
      (node (ref "R14") (pin "1") (pinfunction "A_1") (pintype "passive"))
      (node (ref "R15") (pin "1") (pinfunction "A_1") (pintype "passive"))
      (node (ref "R16") (pin "1") (pinfunction "A_1") (pintype "passive"))
      (node (ref "R17") (pin "1") (pinfunction "A_1") (pintype "passive"))
      (node (ref "R18") (pin "1") (pinfunction "A_1") (pintype "passive"))
      (node (ref "R19") (pin "1") (pinfunction "A_1") (pintype "passive"))
      (node (ref "R20") (pin "1") (pinfunction "A_1") (pintype "passive"))
      (node (ref "R21") (pin "1") (pinfunction "A_1") (pintype "passive"))
      (node (ref "R22") (pin "1") (pinfunction "A_1") (pintype "passive"))
      (node (ref "R23") (pin "1") (pinfunction "A_1") (pintype "passive"))
      (node (ref "R24") (pin "1") (pinfunction "A_1") (pintype "passive"))
      (node (ref "R25") (pin "1") (pinfunction "A_1") (pintype "passive"))
      (node (ref "R26") (pin "1") (pinfunction "A_1") (pintype "passive"))
      (node (ref "R27") (pin "1") (pinfunction "A_1") (pintype "passive"))
      (node (ref "R28") (pin "1") (pinfunction "A_1") (pintype "passive"))
      (node (ref "R5") (pin "1") (pinfunction "A_1") (pintype "passive"))
      (node (ref "R6") (pin "1") (pinfunction "A_1") (pintype "passive"))
      (node (ref "R7") (pin "1") (pinfunction "A_1") (pintype "passive"))
      (node (ref "R8") (pin "1") (pinfunction "A_1") (pintype "passive"))
      (node (ref "R9") (pin "1") (pinfunction "A_1") (pintype "passive"))
      (node (ref "STAB1") (pin "1") (pinfunction "VI_1") (pintype "input"))
      (node (ref "U$20") (pin "P$3") (pinfunction "P$3_P$3") (pintype "bidirectional"))
      (node (ref "U10") (pin "P$2") (pinfunction "S_P$2") (pintype "passive"))
      (node (ref "U10") (pin "P$5") (pinfunction "S_P$5") (pintype "passive"))
      (node (ref "U11") (pin "P$2") (pinfunction "S_P$2") (pintype "passive"))
      (node (ref "U11") (pin "P$5") (pinfunction "S_P$5") (pintype "passive"))
      (node (ref "U12") (pin "P$2") (pinfunction "S_P$2") (pintype "passive"))
      (node (ref "U12") (pin "P$5") (pinfunction "S_P$5") (pintype "passive"))
      (node (ref "U13") (pin "P$2") (pinfunction "S_P$2") (pintype "passive"))
      (node (ref "U13") (pin "P$5") (pinfunction "S_P$5") (pintype "passive"))
      (node (ref "U14") (pin "P$2") (pinfunction "S_P$2") (pintype "passive"))
      (node (ref "U14") (pin "P$5") (pinfunction "S_P$5") (pintype "passive"))
      (node (ref "U15") (pin "P$2") (pinfunction "S_P$2") (pintype "passive"))
      (node (ref "U15") (pin "P$5") (pinfunction "S_P$5") (pintype "passive"))
      (node (ref "U16") (pin "P$2") (pinfunction "S_P$2") (pintype "passive"))
      (node (ref "U16") (pin "P$5") (pinfunction "S_P$5") (pintype "passive"))
      (node (ref "U5") (pin "P$2") (pinfunction "S_P$2") (pintype "passive"))
      (node (ref "U5") (pin "P$5") (pinfunction "S_P$5") (pintype "passive"))
      (node (ref "U6") (pin "P$2") (pinfunction "S_P$2") (pintype "passive"))
      (node (ref "U6") (pin "P$5") (pinfunction "S_P$5") (pintype "passive"))
      (node (ref "U7") (pin "P$2") (pinfunction "S_P$2") (pintype "passive"))
      (node (ref "U7") (pin "P$5") (pinfunction "S_P$5") (pintype "passive"))
      (node (ref "U8") (pin "P$2") (pinfunction "S_P$2") (pintype "passive"))
      (node (ref "U8") (pin "P$5") (pinfunction "S_P$5") (pintype "passive"))
      (node (ref "U9") (pin "P$2") (pinfunction "S_P$2") (pintype "passive"))
      (node (ref "U9") (pin "P$5") (pinfunction "S_P$5") (pintype "passive"))
    )
    (net (code "3") (name "GND") (class "Default")
      (node (ref "C1") (pin "2") (pinfunction "2_2") (pintype "passive"))
      (node (ref "C10") (pin "2") (pinfunction "2_2") (pintype "passive"))
      (node (ref "C11") (pin "2") (pinfunction "2_2") (pintype "passive"))
      (node (ref "C12") (pin "2") (pinfunction "2_2") (pintype "passive"))
      (node (ref "C13") (pin "2") (pinfunction "2_2") (pintype "passive"))
      (node (ref "C14") (pin "2") (pinfunction "2_2") (pintype "passive"))
      (node (ref "C15") (pin "2") (pinfunction "2_2") (pintype "passive"))
      (node (ref "C16") (pin "2") (pinfunction "2_2") (pintype "passive"))
      (node (ref "C17") (pin "2") (pinfunction "2_2") (pintype "passive"))
      (node (ref "C18") (pin "2") (pinfunction "2_2") (pintype "passive"))
      (node (ref "C19") (pin "2") (pinfunction "2_2") (pintype "passive"))
      (node (ref "C2") (pin "2") (pinfunction "2_2") (pintype "passive"))
      (node (ref "C20") (pin "2") (pinfunction "2_2") (pintype "passive"))
      (node (ref "C21") (pin "2") (pinfunction "2_2") (pintype "passive"))
      (node (ref "C22") (pin "2") (pinfunction "2_2") (pintype "passive"))
      (node (ref "C23") (pin "2") (pinfunction "2_2") (pintype "passive"))
      (node (ref "C24") (pin "2") (pinfunction "2_2") (pintype "passive"))
      (node (ref "C25") (pin "2") (pinfunction "2_2") (pintype "passive"))
      (node (ref "C26") (pin "2") (pinfunction "2_2") (pintype "passive"))
      (node (ref "C27") (pin "2") (pinfunction "2_2") (pintype "passive"))
      (node (ref "C28") (pin "2") (pinfunction "2_2") (pintype "passive"))
      (node (ref "C29") (pin "P-") (pinfunction "P-_P-") (pintype "passive"))
      (node (ref "C3") (pin "2") (pinfunction "2_2") (pintype "passive"))
      (node (ref "C30") (pin "2") (pinfunction "2_2") (pintype "passive"))
      (node (ref "C31") (pin "2") (pinfunction "2_2") (pintype "passive"))
      (node (ref "C32") (pin "2") (pinfunction "2_2") (pintype "passive"))
      (node (ref "C33") (pin "1") (pinfunction "1_1") (pintype "passive"))
      (node (ref "C4") (pin "2") (pinfunction "2_2") (pintype "passive"))
      (node (ref "C5") (pin "2") (pinfunction "2_2") (pintype "passive"))
      (node (ref "C6") (pin "2") (pinfunction "2_2") (pintype "passive"))
      (node (ref "C7") (pin "2") (pinfunction "2_2") (pintype "passive"))
      (node (ref "C8") (pin "2") (pinfunction "2_2") (pintype "passive"))
      (node (ref "C9") (pin "2") (pinfunction "2_2") (pintype "passive"))
      (node (ref "CANIC") (pin "2") (pinfunction "VSS_2") (pintype "power_in"))
      (node (ref "CANIC") (pin "8") (pinfunction "RS_8") (pintype "input"))
      (node (ref "CN3") (pin "1") (pinfunction "1_1") (pintype "passive"))
      (node (ref "CN3") (pin "2") (pinfunction "2_2") (pintype "passive"))
      (node (ref "CN_TANIT") (pin "1") (pinfunction "1_1") (pintype "passive"))
      (node (ref "IC1") (pin "2") (pinfunction "GND_2") (pintype "bidirectional"))
      (node (ref "IC2") (pin "2") (pinfunction "GND_2") (pintype "bidirectional"))
      (node (ref "IC3") (pin "2") (pinfunction "GND_2") (pintype "bidirectional"))
      (node (ref "IC4") (pin "2") (pinfunction "GND_2") (pintype "bidirectional"))
      (node (ref "IC5") (pin "2") (pinfunction "GND_2") (pintype "bidirectional"))
      (node (ref "IC6") (pin "2") (pinfunction "GND_2") (pintype "bidirectional"))
      (node (ref "IC7") (pin "1") (pinfunction "01_GND_1") (pintype "power_in"))
      (node (ref "IC7") (pin "13") (pinfunction "13_~{OE}_13") (pintype "input"))
      (node (ref "IC8") (pin "1") (pinfunction "01_GND_1") (pintype "power_in"))
      (node (ref "IC8") (pin "13") (pinfunction "13_~{OE}_13") (pintype "input"))
      (node (ref "IC9") (pin "1") (pinfunction "01_GND_1") (pintype "power_in"))
      (node (ref "IC9") (pin "13") (pinfunction "13_~{OE}_13") (pintype "input"))
      (node (ref "PIC1") (pin "29") (pinfunction "VSS_29") (pintype "power_in"))
      (node (ref "PIC1") (pin "6") (pinfunction "VSS_2_6") (pintype "power_in"))
      (node (ref "R2") (pin "1") (pinfunction "A_1") (pintype "passive"))
      (node (ref "R3") (pin "1") (pinfunction "A_1") (pintype "passive"))
      (node (ref "R4") (pin "1") (pinfunction "A_1") (pintype "passive"))
      (node (ref "STAB1") (pin "3") (pinfunction "GND_3") (pintype "passive"))
      (node (ref "U$1") (pin "P$1") (pinfunction "P$1_P$1") (pintype "bidirectional"))
      (node (ref "U$20") (pin "P$1") (pinfunction "P$1_P$1") (pintype "bidirectional"))
      (node (ref "ZOLD_3P1") (pin "1") (pinfunction "1_1") (pintype "passive"))
      (node (ref "ZOLD_3P10") (pin "1") (pinfunction "1_1") (pintype "passive"))
      (node (ref "ZOLD_3P11") (pin "1") (pinfunction "1_1") (pintype "passive"))
      (node (ref "ZOLD_3P12") (pin "1") (pinfunction "1_1") (pintype "passive"))
      (node (ref "ZOLD_3P2") (pin "1") (pinfunction "1_1") (pintype "passive"))
      (node (ref "ZOLD_3P3") (pin "1") (pinfunction "1_1") (pintype "passive"))
      (node (ref "ZOLD_3P4") (pin "1") (pinfunction "1_1") (pintype "passive"))
      (node (ref "ZOLD_3P5") (pin "1") (pinfunction "1_1") (pintype "passive"))
      (node (ref "ZOLD_3P6") (pin "1") (pinfunction "1_1") (pintype "passive"))
      (node (ref "ZOLD_3P7") (pin "1") (pinfunction "1_1") (pintype "passive"))
      (node (ref "ZOLD_3P8") (pin "1") (pinfunction "1_1") (pintype "passive"))
      (node (ref "ZOLD_3P9") (pin "1") (pinfunction "1_1") (pintype "passive"))
    )
    (net (code "4") (name "Net-(CANIC-CANH)") (class "Default")
      (node (ref "CANIC") (pin "7") (pinfunction "CANH_7") (pintype "bidirectional"))
      (node (ref "CN_CANLEZAR") (pin "2") (pinfunction "2_2") (pintype "passive"))
      (node (ref "CN_RJ1") (pin "5") (pinfunction "5_5") (pintype "passive"))
      (node (ref "CN_RJ2") (pin "5") (pinfunction "5_5") (pintype "passive"))
      (node (ref "U$1") (pin "P$2") (pinfunction "P$2_P$2") (pintype "bidirectional"))
    )
    (net (code "5") (name "Net-(CANIC-CANL)") (class "Default")
      (node (ref "CANIC") (pin "6") (pinfunction "CANL_6") (pintype "bidirectional"))
      (node (ref "CN_RJ1") (pin "4") (pinfunction "4_4") (pintype "passive"))
      (node (ref "CN_RJ2") (pin "4") (pinfunction "4_4") (pintype "passive"))
      (node (ref "R125") (pin "1") (pinfunction "A_1") (pintype "passive"))
      (node (ref "R126") (pin "2") (pinfunction "E_2") (pintype "passive"))
      (node (ref "U$1") (pin "P$3") (pinfunction "P$3_P$3") (pintype "bidirectional"))
    )
    (net (code "6") (name "Net-(CANIC-RXD)") (class "Default")
      (node (ref "CANIC") (pin "4") (pinfunction "RXD_4") (pintype "output"))
      (node (ref "PIC1") (pin "11") (pinfunction "RB3/CANRX_11") (pintype "bidirectional"))
    )
    (net (code "7") (name "Net-(CANIC-TXD)") (class "Default")
      (node (ref "CANIC") (pin "1") (pinfunction "TXD_1") (pintype "input"))
      (node (ref "PIC1") (pin "10") (pinfunction "RB2/INT2/CANTX_10") (pintype "bidirectional"))
    )
    (net (code "8") (name "Net-(CN3-Pad10)") (class "Default")
      (node (ref "CN3") (pin "10") (pinfunction "10_10") (pintype "passive"))
      (node (ref "CN3") (pin "9") (pinfunction "9_9") (pintype "passive"))
    )
    (net (code "9") (name "Net-(CN_RJ1-Pad7)") (class "Default")
      (node (ref "CN_RJ1") (pin "7") (pinfunction "7_7") (pintype "passive"))
      (node (ref "CN_RJ2") (pin "7") (pinfunction "7_7") (pintype "passive"))
      (node (ref "U$21") (pin "P$1") (pinfunction "P$1_P$1") (pintype "bidirectional"))
    )
    (net (code "10") (name "Net-(CN_RJ1-Pad8)") (class "Default")
      (node (ref "CN_RJ1") (pin "8") (pinfunction "8_8") (pintype "passive"))
      (node (ref "D2") (pin "C") (pinfunction "C_C") (pintype "passive"))
    )
    (net (code "11") (name "Net-(CN_RJ2-Pad8)") (class "Default")
      (node (ref "CN_RJ2") (pin "8") (pinfunction "8_8") (pintype "passive"))
      (node (ref "D1") (pin "C") (pinfunction "C_C") (pintype "passive"))
    )
    (net (code "12") (name "Net-(D1-PadA)") (class "Default")
      (node (ref "D1") (pin "A") (pinfunction "A_A") (pintype "passive"))
      (node (ref "D2") (pin "A") (pinfunction "A_A") (pintype "passive"))
      (node (ref "U$21") (pin "P$2") (pinfunction "P$2_P$2") (pintype "bidirectional"))
    )
    (net (code "13") (name "Net-(IC1-I{slash}O1)") (class "Default")
      (node (ref "C4") (pin "1") (pinfunction "1_1") (pintype "passive"))
      (node (ref "IC1") (pin "1") (pinfunction "I/O1_1") (pintype "bidirectional"))
      (node (ref "R101") (pin "2") (pinfunction "E_2") (pintype "passive"))
      (node (ref "R53") (pin "1") (pinfunction "A_1") (pintype "passive"))
    )
    (net (code "14") (name "Net-(IC1-I{slash}O2)") (class "Default")
      (node (ref "C5") (pin "1") (pinfunction "1_1") (pintype "passive"))
      (node (ref "IC1") (pin "3") (pinfunction "I/O2_3") (pintype "bidirectional"))
      (node (ref "R102") (pin "2") (pinfunction "E_2") (pintype "passive"))
      (node (ref "R54") (pin "1") (pinfunction "A_1") (pintype "passive"))
    )
    (net (code "15") (name "Net-(IC1-I{slash}O3)") (class "Default")
      (node (ref "C6") (pin "1") (pinfunction "1_1") (pintype "passive"))
      (node (ref "IC1") (pin "4") (pinfunction "I/O3_4") (pintype "bidirectional"))
      (node (ref "R103") (pin "2") (pinfunction "E_2") (pintype "passive"))
      (node (ref "R55") (pin "1") (pinfunction "A_1") (pintype "passive"))
    )
    (net (code "16") (name "Net-(IC1-I{slash}O4)") (class "Default")
      (node (ref "C7") (pin "1") (pinfunction "1_1") (pintype "passive"))
      (node (ref "IC1") (pin "6") (pinfunction "I/O4_6") (pintype "bidirectional"))
      (node (ref "R104") (pin "2") (pinfunction "E_2") (pintype "passive"))
      (node (ref "R56") (pin "1") (pinfunction "A_1") (pintype "passive"))
    )
    (net (code "17") (name "Net-(IC2-I{slash}O1)") (class "Default")
      (node (ref "C8") (pin "1") (pinfunction "1_1") (pintype "passive"))
      (node (ref "IC2") (pin "1") (pinfunction "I/O1_1") (pintype "bidirectional"))
      (node (ref "R105") (pin "2") (pinfunction "E_2") (pintype "passive"))
      (node (ref "R57") (pin "1") (pinfunction "A_1") (pintype "passive"))
    )
    (net (code "18") (name "Net-(IC2-I{slash}O2)") (class "Default")
      (node (ref "C9") (pin "1") (pinfunction "1_1") (pintype "passive"))
      (node (ref "IC2") (pin "3") (pinfunction "I/O2_3") (pintype "bidirectional"))
      (node (ref "R106") (pin "2") (pinfunction "E_2") (pintype "passive"))
      (node (ref "R58") (pin "1") (pinfunction "A_1") (pintype "passive"))
    )
    (net (code "19") (name "Net-(IC2-I{slash}O3)") (class "Default")
      (node (ref "C10") (pin "1") (pinfunction "1_1") (pintype "passive"))
      (node (ref "IC2") (pin "4") (pinfunction "I/O3_4") (pintype "bidirectional"))
      (node (ref "R107") (pin "2") (pinfunction "E_2") (pintype "passive"))
      (node (ref "R59") (pin "1") (pinfunction "A_1") (pintype "passive"))
    )
    (net (code "20") (name "Net-(IC2-I{slash}O4)") (class "Default")
      (node (ref "C11") (pin "1") (pinfunction "1_1") (pintype "passive"))
      (node (ref "IC2") (pin "6") (pinfunction "I/O4_6") (pintype "bidirectional"))
      (node (ref "R108") (pin "2") (pinfunction "E_2") (pintype "passive"))
      (node (ref "R60") (pin "1") (pinfunction "A_1") (pintype "passive"))
    )
    (net (code "21") (name "Net-(IC3-I{slash}O1)") (class "Default")
      (node (ref "C12") (pin "1") (pinfunction "1_1") (pintype "passive"))
      (node (ref "IC3") (pin "1") (pinfunction "I/O1_1") (pintype "bidirectional"))
      (node (ref "R109") (pin "2") (pinfunction "E_2") (pintype "passive"))
      (node (ref "R61") (pin "1") (pinfunction "A_1") (pintype "passive"))
    )
    (net (code "22") (name "Net-(IC3-I{slash}O2)") (class "Default")
      (node (ref "C13") (pin "1") (pinfunction "1_1") (pintype "passive"))
      (node (ref "IC3") (pin "3") (pinfunction "I/O2_3") (pintype "bidirectional"))
      (node (ref "R110") (pin "2") (pinfunction "E_2") (pintype "passive"))
      (node (ref "R62") (pin "1") (pinfunction "A_1") (pintype "passive"))
    )
    (net (code "23") (name "Net-(IC3-I{slash}O3)") (class "Default")
      (node (ref "C14") (pin "1") (pinfunction "1_1") (pintype "passive"))
      (node (ref "IC3") (pin "4") (pinfunction "I/O3_4") (pintype "bidirectional"))
      (node (ref "R111") (pin "2") (pinfunction "E_2") (pintype "passive"))
      (node (ref "R63") (pin "1") (pinfunction "A_1") (pintype "passive"))
    )
    (net (code "24") (name "Net-(IC3-I{slash}O4)") (class "Default")
      (node (ref "C15") (pin "1") (pinfunction "1_1") (pintype "passive"))
      (node (ref "IC3") (pin "6") (pinfunction "I/O4_6") (pintype "bidirectional"))
      (node (ref "R112") (pin "2") (pinfunction "E_2") (pintype "passive"))
      (node (ref "R64") (pin "1") (pinfunction "A_1") (pintype "passive"))
    )
    (net (code "25") (name "Net-(IC4-I{slash}O1)") (class "Default")
      (node (ref "C16") (pin "1") (pinfunction "1_1") (pintype "passive"))
      (node (ref "IC4") (pin "1") (pinfunction "I/O1_1") (pintype "bidirectional"))
      (node (ref "R113") (pin "2") (pinfunction "E_2") (pintype "passive"))
      (node (ref "R65") (pin "1") (pinfunction "A_1") (pintype "passive"))
    )
    (net (code "26") (name "Net-(IC4-I{slash}O2)") (class "Default")
      (node (ref "C17") (pin "1") (pinfunction "1_1") (pintype "passive"))
      (node (ref "IC4") (pin "3") (pinfunction "I/O2_3") (pintype "bidirectional"))
      (node (ref "R114") (pin "2") (pinfunction "E_2") (pintype "passive"))
      (node (ref "R66") (pin "1") (pinfunction "A_1") (pintype "passive"))
    )
    (net (code "27") (name "Net-(IC4-I{slash}O3)") (class "Default")
      (node (ref "C18") (pin "1") (pinfunction "1_1") (pintype "passive"))
      (node (ref "IC4") (pin "4") (pinfunction "I/O3_4") (pintype "bidirectional"))
      (node (ref "R115") (pin "2") (pinfunction "E_2") (pintype "passive"))
      (node (ref "R67") (pin "1") (pinfunction "A_1") (pintype "passive"))
    )
    (net (code "28") (name "Net-(IC4-I{slash}O4)") (class "Default")
      (node (ref "C19") (pin "1") (pinfunction "1_1") (pintype "passive"))
      (node (ref "IC4") (pin "6") (pinfunction "I/O4_6") (pintype "bidirectional"))
      (node (ref "R116") (pin "2") (pinfunction "E_2") (pintype "passive"))
      (node (ref "R68") (pin "1") (pinfunction "A_1") (pintype "passive"))
    )
    (net (code "29") (name "Net-(IC5-I{slash}O1)") (class "Default")
      (node (ref "C20") (pin "1") (pinfunction "1_1") (pintype "passive"))
      (node (ref "IC5") (pin "1") (pinfunction "I/O1_1") (pintype "bidirectional"))
      (node (ref "R117") (pin "2") (pinfunction "E_2") (pintype "passive"))
      (node (ref "R69") (pin "1") (pinfunction "A_1") (pintype "passive"))
    )
    (net (code "30") (name "Net-(IC5-I{slash}O2)") (class "Default")
      (node (ref "C21") (pin "1") (pinfunction "1_1") (pintype "passive"))
      (node (ref "IC5") (pin "3") (pinfunction "I/O2_3") (pintype "bidirectional"))
      (node (ref "R118") (pin "2") (pinfunction "E_2") (pintype "passive"))
      (node (ref "R70") (pin "1") (pinfunction "A_1") (pintype "passive"))
    )
    (net (code "31") (name "Net-(IC5-I{slash}O3)") (class "Default")
      (node (ref "C22") (pin "1") (pinfunction "1_1") (pintype "passive"))
      (node (ref "IC5") (pin "4") (pinfunction "I/O3_4") (pintype "bidirectional"))
      (node (ref "R119") (pin "2") (pinfunction "E_2") (pintype "passive"))
      (node (ref "R71") (pin "1") (pinfunction "A_1") (pintype "passive"))
    )
    (net (code "32") (name "Net-(IC5-I{slash}O4)") (class "Default")
      (node (ref "C23") (pin "1") (pinfunction "1_1") (pintype "passive"))
      (node (ref "IC5") (pin "6") (pinfunction "I/O4_6") (pintype "bidirectional"))
      (node (ref "R120") (pin "2") (pinfunction "E_2") (pintype "passive"))
      (node (ref "R72") (pin "1") (pinfunction "A_1") (pintype "passive"))
    )
    (net (code "33") (name "Net-(IC6-I{slash}O1)") (class "Default")
      (node (ref "C24") (pin "1") (pinfunction "1_1") (pintype "passive"))
      (node (ref "IC6") (pin "1") (pinfunction "I/O1_1") (pintype "bidirectional"))
      (node (ref "R121") (pin "2") (pinfunction "E_2") (pintype "passive"))
      (node (ref "R73") (pin "1") (pinfunction "A_1") (pintype "passive"))
    )
    (net (code "34") (name "Net-(IC6-I{slash}O2)") (class "Default")
      (node (ref "C25") (pin "1") (pinfunction "1_1") (pintype "passive"))
      (node (ref "IC6") (pin "3") (pinfunction "I/O2_3") (pintype "bidirectional"))
      (node (ref "R122") (pin "2") (pinfunction "E_2") (pintype "passive"))
      (node (ref "R74") (pin "1") (pinfunction "A_1") (pintype "passive"))
    )
    (net (code "35") (name "Net-(IC6-I{slash}O3)") (class "Default")
      (node (ref "C26") (pin "1") (pinfunction "1_1") (pintype "passive"))
      (node (ref "IC6") (pin "4") (pinfunction "I/O3_4") (pintype "bidirectional"))
      (node (ref "R123") (pin "2") (pinfunction "E_2") (pintype "passive"))
      (node (ref "R75") (pin "1") (pinfunction "A_1") (pintype "passive"))
    )
    (net (code "36") (name "Net-(IC6-I{slash}O4)") (class "Default")
      (node (ref "C27") (pin "1") (pinfunction "1_1") (pintype "passive"))
      (node (ref "IC6") (pin "6") (pinfunction "I/O4_6") (pintype "bidirectional"))
      (node (ref "R124") (pin "2") (pinfunction "E_2") (pintype "passive"))
      (node (ref "R76") (pin "1") (pinfunction "A_1") (pintype "passive"))
    )
    (net (code "37") (name "Net-(IC7-02_SDI)") (class "Default")
      (node (ref "IC7") (pin "2") (pinfunction "02_SDI_2") (pintype "input"))
      (node (ref "PIC1") (pin "43") (pinfunction "RC5/SDO_43") (pintype "bidirectional"))
    )
    (net (code "38") (name "Net-(IC7-03_CLK)") (class "Default")
      (node (ref "IC7") (pin "3") (pinfunction "03_CLK_3") (pintype "input"))
      (node (ref "IC8") (pin "3") (pinfunction "03_CLK_3") (pintype "input"))
      (node (ref "IC9") (pin "3") (pinfunction "03_CLK_3") (pintype "input"))
      (node (ref "PIC1") (pin "37") (pinfunction "RC3/SCK/SCL_37") (pintype "bidirectional"))
    )
    (net (code "39") (name "Net-(IC7-04_~{LA})") (class "Default")
      (node (ref "IC7") (pin "4") (pinfunction "04_~{LA}_4") (pintype "input"))
      (node (ref "IC8") (pin "4") (pinfunction "04_~{LA}_4") (pintype "input"))
      (node (ref "IC9") (pin "4") (pinfunction "04_~{LA}_4") (pintype "input"))
      (node (ref "PIC1") (pin "36") (pinfunction "RC2/CCP1_36") (pintype "bidirectional"))
    )
    (net (code "40") (name "Net-(IC7-05_OUT0)") (class "Default")
      (node (ref "IC7") (pin "5") (pinfunction "05_OUT0_5") (pintype "output"))
      (node (ref "R5") (pin "2") (pinfunction "E_2") (pintype "passive"))
      (node (ref "U5") (pin "P$1") (pinfunction "G_P$1") (pintype "passive"))
    )
    (net (code "41") (name "Net-(IC7-06_OUT1)") (class "Default")
      (node (ref "IC7") (pin "6") (pinfunction "06_OUT1_6") (pintype "output"))
      (node (ref "R6") (pin "2") (pinfunction "E_2") (pintype "passive"))
      (node (ref "U5") (pin "P$3") (pinfunction "G_P$3") (pintype "passive"))
    )
    (net (code "42") (name "Net-(IC7-07_OUT2)") (class "Default")
      (node (ref "IC7") (pin "7") (pinfunction "07_OUT2_7") (pintype "output"))
      (node (ref "R7") (pin "2") (pinfunction "E_2") (pintype "passive"))
      (node (ref "U6") (pin "P$1") (pinfunction "G_P$1") (pintype "passive"))
    )
    (net (code "43") (name "Net-(IC7-08_OUT3)") (class "Default")
      (node (ref "IC7") (pin "8") (pinfunction "08_OUT3_8") (pintype "output"))
      (node (ref "R8") (pin "2") (pinfunction "E_2") (pintype "passive"))
      (node (ref "U6") (pin "P$3") (pinfunction "G_P$3") (pintype "passive"))
    )
    (net (code "44") (name "Net-(IC7-09_OUT4)") (class "Default")
      (node (ref "IC7") (pin "9") (pinfunction "09_OUT4_9") (pintype "output"))
      (node (ref "R9") (pin "2") (pinfunction "E_2") (pintype "passive"))
      (node (ref "U7") (pin "P$1") (pinfunction "G_P$1") (pintype "passive"))
    )
    (net (code "45") (name "Net-(IC7-10_OUT5)") (class "Default")
      (node (ref "IC7") (pin "10") (pinfunction "10_OUT5_10") (pintype "output"))
      (node (ref "R10") (pin "2") (pinfunction "E_2") (pintype "passive"))
      (node (ref "U7") (pin "P$3") (pinfunction "G_P$3") (pintype "passive"))
    )
    (net (code "46") (name "Net-(IC7-11_OUT6)") (class "Default")
      (node (ref "IC7") (pin "11") (pinfunction "11_OUT6_11") (pintype "output"))
      (node (ref "R11") (pin "2") (pinfunction "E_2") (pintype "passive"))
      (node (ref "U8") (pin "P$1") (pinfunction "G_P$1") (pintype "passive"))
    )
    (net (code "47") (name "Net-(IC7-12_OUT7)") (class "Default")
      (node (ref "IC7") (pin "12") (pinfunction "12_OUT7_12") (pintype "output"))
      (node (ref "R12") (pin "2") (pinfunction "E_2") (pintype "passive"))
      (node (ref "U8") (pin "P$3") (pinfunction "G_P$3") (pintype "passive"))
    )
    (net (code "48") (name "Net-(IC7-14_SDO)") (class "Default")
      (node (ref "IC7") (pin "14") (pinfunction "14_SDO_14") (pintype "output"))
      (node (ref "IC8") (pin "2") (pinfunction "02_SDI_2") (pintype "input"))
    )
    (net (code "49") (name "Net-(IC7-15_REXT)") (class "Default")
      (node (ref "IC7") (pin "15") (pinfunction "15_REXT_15") (pintype "bidirectional"))
      (node (ref "R2") (pin "2") (pinfunction "E_2") (pintype "passive"))
    )
    (net (code "50") (name "Net-(IC8-05_OUT0)") (class "Default")
      (node (ref "IC8") (pin "5") (pinfunction "05_OUT0_5") (pintype "output"))
      (node (ref "R13") (pin "2") (pinfunction "E_2") (pintype "passive"))
      (node (ref "U9") (pin "P$1") (pinfunction "G_P$1") (pintype "passive"))
    )
    (net (code "51") (name "Net-(IC8-06_OUT1)") (class "Default")
      (node (ref "IC8") (pin "6") (pinfunction "06_OUT1_6") (pintype "output"))
      (node (ref "R14") (pin "2") (pinfunction "E_2") (pintype "passive"))
      (node (ref "U9") (pin "P$3") (pinfunction "G_P$3") (pintype "passive"))
    )
    (net (code "52") (name "Net-(IC8-07_OUT2)") (class "Default")
      (node (ref "IC8") (pin "7") (pinfunction "07_OUT2_7") (pintype "output"))
      (node (ref "R15") (pin "2") (pinfunction "E_2") (pintype "passive"))
      (node (ref "U10") (pin "P$1") (pinfunction "G_P$1") (pintype "passive"))
    )
    (net (code "53") (name "Net-(IC8-08_OUT3)") (class "Default")
      (node (ref "IC8") (pin "8") (pinfunction "08_OUT3_8") (pintype "output"))
      (node (ref "R16") (pin "2") (pinfunction "E_2") (pintype "passive"))
      (node (ref "U10") (pin "P$3") (pinfunction "G_P$3") (pintype "passive"))
    )
    (net (code "54") (name "Net-(IC8-09_OUT4)") (class "Default")
      (node (ref "IC8") (pin "9") (pinfunction "09_OUT4_9") (pintype "output"))
      (node (ref "R17") (pin "2") (pinfunction "E_2") (pintype "passive"))
      (node (ref "U11") (pin "P$1") (pinfunction "G_P$1") (pintype "passive"))
    )
    (net (code "55") (name "Net-(IC8-10_OUT5)") (class "Default")
      (node (ref "IC8") (pin "10") (pinfunction "10_OUT5_10") (pintype "output"))
      (node (ref "R18") (pin "2") (pinfunction "E_2") (pintype "passive"))
      (node (ref "U11") (pin "P$3") (pinfunction "G_P$3") (pintype "passive"))
    )
    (net (code "56") (name "Net-(IC8-11_OUT6)") (class "Default")
      (node (ref "IC8") (pin "11") (pinfunction "11_OUT6_11") (pintype "output"))
      (node (ref "R19") (pin "2") (pinfunction "E_2") (pintype "passive"))
      (node (ref "U12") (pin "P$1") (pinfunction "G_P$1") (pintype "passive"))
    )
    (net (code "57") (name "Net-(IC8-12_OUT7)") (class "Default")
      (node (ref "IC8") (pin "12") (pinfunction "12_OUT7_12") (pintype "output"))
      (node (ref "R20") (pin "2") (pinfunction "E_2") (pintype "passive"))
      (node (ref "U12") (pin "P$3") (pinfunction "G_P$3") (pintype "passive"))
    )
    (net (code "58") (name "Net-(IC8-14_SDO)") (class "Default")
      (node (ref "IC8") (pin "14") (pinfunction "14_SDO_14") (pintype "output"))
      (node (ref "IC9") (pin "2") (pinfunction "02_SDI_2") (pintype "input"))
    )
    (net (code "59") (name "Net-(IC8-15_REXT)") (class "Default")
      (node (ref "IC8") (pin "15") (pinfunction "15_REXT_15") (pintype "bidirectional"))
      (node (ref "R3") (pin "2") (pinfunction "E_2") (pintype "passive"))
    )
    (net (code "60") (name "Net-(IC9-05_OUT0)") (class "Default")
      (node (ref "IC9") (pin "5") (pinfunction "05_OUT0_5") (pintype "output"))
      (node (ref "R21") (pin "2") (pinfunction "E_2") (pintype "passive"))
      (node (ref "U13") (pin "P$1") (pinfunction "G_P$1") (pintype "passive"))
    )
    (net (code "61") (name "Net-(IC9-06_OUT1)") (class "Default")
      (node (ref "IC9") (pin "6") (pinfunction "06_OUT1_6") (pintype "output"))
      (node (ref "R22") (pin "2") (pinfunction "E_2") (pintype "passive"))
      (node (ref "U13") (pin "P$3") (pinfunction "G_P$3") (pintype "passive"))
    )
    (net (code "62") (name "Net-(IC9-07_OUT2)") (class "Default")
      (node (ref "IC9") (pin "7") (pinfunction "07_OUT2_7") (pintype "output"))
      (node (ref "R23") (pin "2") (pinfunction "E_2") (pintype "passive"))
      (node (ref "U14") (pin "P$1") (pinfunction "G_P$1") (pintype "passive"))
    )
    (net (code "63") (name "Net-(IC9-08_OUT3)") (class "Default")
      (node (ref "IC9") (pin "8") (pinfunction "08_OUT3_8") (pintype "output"))
      (node (ref "R24") (pin "2") (pinfunction "E_2") (pintype "passive"))
      (node (ref "U14") (pin "P$3") (pinfunction "G_P$3") (pintype "passive"))
    )
    (net (code "64") (name "Net-(IC9-09_OUT4)") (class "Default")
      (node (ref "IC9") (pin "9") (pinfunction "09_OUT4_9") (pintype "output"))
      (node (ref "R25") (pin "2") (pinfunction "E_2") (pintype "passive"))
      (node (ref "U15") (pin "P$1") (pinfunction "G_P$1") (pintype "passive"))
    )
    (net (code "65") (name "Net-(IC9-10_OUT5)") (class "Default")
      (node (ref "IC9") (pin "10") (pinfunction "10_OUT5_10") (pintype "output"))
      (node (ref "R26") (pin "2") (pinfunction "E_2") (pintype "passive"))
      (node (ref "U15") (pin "P$3") (pinfunction "G_P$3") (pintype "passive"))
    )
    (net (code "66") (name "Net-(IC9-11_OUT6)") (class "Default")
      (node (ref "IC9") (pin "11") (pinfunction "11_OUT6_11") (pintype "output"))
      (node (ref "R27") (pin "2") (pinfunction "E_2") (pintype "passive"))
      (node (ref "U16") (pin "P$1") (pinfunction "G_P$1") (pintype "passive"))
    )
    (net (code "67") (name "Net-(IC9-12_OUT7)") (class "Default")
      (node (ref "IC9") (pin "12") (pinfunction "12_OUT7_12") (pintype "output"))
      (node (ref "R28") (pin "2") (pinfunction "E_2") (pintype "passive"))
      (node (ref "U16") (pin "P$3") (pinfunction "G_P$3") (pintype "passive"))
    )
    (net (code "68") (name "Net-(IC9-15_REXT)") (class "Default")
      (node (ref "IC9") (pin "15") (pinfunction "15_REXT_15") (pintype "bidirectional"))
      (node (ref "R4") (pin "2") (pinfunction "E_2") (pintype "passive"))
    )
    (net (code "69") (name "Net-(PIC1-OSC1{slash}CLKI{slash}RA7)") (class "Default")
      (node (ref "C2") (pin "1") (pinfunction "1_1") (pintype "passive"))
      (node (ref "PIC1") (pin "30") (pinfunction "OSC1/CLKI/RA7_30") (pintype "bidirectional"))
      (node (ref "Q1") (pin "1") (pinfunction "1_1") (pintype "passive"))
    )
    (net (code "70") (name "Net-(PIC1-OSC2{slash}CLKO{slash}RA6)") (class "Default")
      (node (ref "C1") (pin "1") (pinfunction "1_1") (pintype "passive"))
      (node (ref "PIC1") (pin "31") (pinfunction "OSC2/CLKO/RA6_31") (pintype "bidirectional"))
      (node (ref "Q1") (pin "2") (pinfunction "2_2") (pintype "passive"))
    )
    (net (code "71") (name "Net-(PIC1-RA0{slash}AN0{slash}CVREF)") (class "Default")
      (node (ref "PIC1") (pin "19") (pinfunction "RA0/AN0/CVREF_19") (pintype "bidirectional"))
      (node (ref "R112") (pin "1") (pinfunction "A_1") (pintype "passive"))
    )
    (net (code "72") (name "Net-(PIC1-RA1{slash}AN1)") (class "Default")
      (node (ref "PIC1") (pin "20") (pinfunction "RA1/AN1_20") (pintype "bidirectional"))
      (node (ref "R113") (pin "1") (pinfunction "A_1") (pintype "passive"))
    )
    (net (code "73") (name "Net-(PIC1-RA2{slash}AN2{slash}VREF-)") (class "Default")
      (node (ref "PIC1") (pin "21") (pinfunction "RA2/AN2/VREF-_21") (pintype "bidirectional"))
      (node (ref "R107") (pin "1") (pinfunction "A_1") (pintype "passive"))
    )
    (net (code "74") (name "Net-(PIC1-RA3{slash}AN3{slash}VREF+)") (class "Default")
      (node (ref "PIC1") (pin "22") (pinfunction "RA3/AN3/VREF+_22") (pintype "bidirectional"))
      (node (ref "R116") (pin "1") (pinfunction "A_1") (pintype "passive"))
    )
    (net (code "75") (name "Net-(PIC1-RA5{slash}AN4{slash}~{SS{slash}HLVDIN})") (class "Default")
      (node (ref "PIC1") (pin "24") (pinfunction "RA5/AN4/~{SS/HLVDIN}_24") (pintype "bidirectional"))
      (node (ref "R108") (pin "1") (pinfunction "A_1") (pintype "passive"))
    )
    (net (code "76") (name "Net-(PIC1-RB0{slash}INT0{slash}FLT0{slash}AN10)") (class "Default")
      (node (ref "PIC1") (pin "8") (pinfunction "RB0/INT0/FLT0/AN10_8") (pintype "bidirectional"))
      (node (ref "R122") (pin "1") (pinfunction "A_1") (pintype "passive"))
    )
    (net (code "77") (name "Net-(PIC1-RB1{slash}INT1{slash}AN8)") (class "Default")
      (node (ref "PIC1") (pin "9") (pinfunction "RB1/INT1/AN8_9") (pintype "bidirectional"))
      (node (ref "R123") (pin "1") (pinfunction "A_1") (pintype "passive"))
    )
    (net (code "78") (name "Net-(PIC1-RB4{slash}KBI0{slash}AN9)") (class "Default")
      (node (ref "PIC1") (pin "14") (pinfunction "RB4/KBI0/AN9_14") (pintype "bidirectional"))
      (node (ref "R124") (pin "1") (pinfunction "A_1") (pintype "passive"))
    )
    (net (code "79") (name "Net-(PIC1-RB5{slash}KBI1{slash}PGM)") (class "Default")
      (node (ref "PIC1") (pin "15") (pinfunction "RB5/KBI1/PGM_15") (pintype "bidirectional"))
      (node (ref "R109") (pin "1") (pinfunction "A_1") (pintype "passive"))
    )
    (net (code "80") (name "Net-(PIC1-RB6{slash}KBI2{slash}PGC)") (class "Default")
      (node (ref "CN3") (pin "5") (pinfunction "5_5") (pintype "passive"))
      (node (ref "CN3") (pin "6") (pinfunction "6_6") (pintype "passive"))
      (node (ref "CN_TANIT") (pin "5") (pinfunction "5_5") (pintype "passive"))
      (node (ref "PIC1") (pin "16") (pinfunction "RB6/KBI2/PGC_16") (pintype "bidirectional"))
    )
    (net (code "81") (name "Net-(PIC1-RB7{slash}KBI3{slash}PGD)") (class "Default")
      (node (ref "CN3") (pin "7") (pinfunction "7_7") (pintype "passive"))
      (node (ref "CN3") (pin "8") (pinfunction "8_8") (pintype "passive"))
      (node (ref "CN_TANIT") (pin "4") (pinfunction "4_4") (pintype "passive"))
      (node (ref "PIC1") (pin "17") (pinfunction "RB7/KBI3/PGD_17") (pintype "bidirectional"))
    )
    (net (code "82") (name "Net-(PIC1-RC0{slash}T1OSO{slash}T13CKI)") (class "Default")
      (node (ref "PIC1") (pin "32") (pinfunction "RC0/T1OSO/T13CKI_32") (pintype "bidirectional"))
      (node (ref "R114") (pin "1") (pinfunction "A_1") (pintype "passive"))
    )
    (net (code "83") (name "Net-(PIC1-RC1{slash}T1OSI)") (class "Default")
      (node (ref "PIC1") (pin "35") (pinfunction "RC1/T1OSI_35") (pintype "bidirectional"))
      (node (ref "R115") (pin "1") (pinfunction "A_1") (pintype "passive"))
    )
    (net (code "84") (name "Net-(PIC1-RC4{slash}SDI{slash}SDA)") (class "Default")
      (node (ref "PIC1") (pin "42") (pinfunction "RC4/SDI/SDA_42") (pintype "bidirectional"))
      (node (ref "R102") (pin "1") (pinfunction "A_1") (pintype "passive"))
    )
    (net (code "85") (name "Net-(PIC1-RC6{slash}TX{slash}CK)") (class "Default")
      (node (ref "PIC1") (pin "44") (pinfunction "RC6/TX/CK_44") (pintype "bidirectional"))
      (node (ref "R101") (pin "1") (pinfunction "A_1") (pintype "passive"))
    )
    (net (code "86") (name "Net-(PIC1-RC7{slash}RX{slash}DT)") (class "Default")
      (node (ref "PIC1") (pin "1") (pinfunction "RC7/RX/DT_1") (pintype "bidirectional"))
      (node (ref "R117") (pin "1") (pinfunction "A_1") (pintype "passive"))
    )
    (net (code "87") (name "Net-(PIC1-RD0{slash}PSP0{slash}C1IN+)") (class "Default")
      (node (ref "PIC1") (pin "38") (pinfunction "RD0/PSP0/C1IN+_38") (pintype "bidirectional"))
      (node (ref "R104") (pin "1") (pinfunction "A_1") (pintype "passive"))
    )
    (net (code "88") (name "Net-(PIC1-RD1{slash}PSP1{slash}C1IN-)") (class "Default")
      (node (ref "PIC1") (pin "39") (pinfunction "RD1/PSP1/C1IN-_39") (pintype "bidirectional"))
      (node (ref "R103") (pin "1") (pinfunction "A_1") (pintype "passive"))
    )
    (net (code "89") (name "Net-(PIC1-RD2{slash}PSP2{slash}C2IN+)") (class "Default")
      (node (ref "PIC1") (pin "40") (pinfunction "RD2/PSP2/C2IN+_40") (pintype "bidirectional"))
      (node (ref "R111") (pin "1") (pinfunction "A_1") (pintype "passive"))
    )
    (net (code "90") (name "Net-(PIC1-RD3{slash}PSP3{slash}C2IN-)") (class "Default")
      (node (ref "PIC1") (pin "41") (pinfunction "RD3/PSP3/C2IN-_41") (pintype "bidirectional"))
      (node (ref "R110") (pin "1") (pinfunction "A_1") (pintype "passive"))
    )
    (net (code "91") (name "Net-(PIC1-RD4{slash}PSP4{slash}ECCP1{slash}P1A)") (class "Default")
      (node (ref "PIC1") (pin "2") (pinfunction "RD4/PSP4/ECCP1/P1A_2") (pintype "bidirectional"))
      (node (ref "R118") (pin "1") (pinfunction "A_1") (pintype "passive"))
    )
    (net (code "92") (name "Net-(PIC1-RD5{slash}PSP5{slash}P1B)") (class "Default")
      (node (ref "PIC1") (pin "3") (pinfunction "RD5/PSP5/P1B_3") (pintype "bidirectional"))
      (node (ref "R119") (pin "1") (pinfunction "A_1") (pintype "passive"))
    )
    (net (code "93") (name "Net-(PIC1-RD6{slash}PSP6{slash}P1C)") (class "Default")
      (node (ref "PIC1") (pin "4") (pinfunction "RD6/PSP6/P1C_4") (pintype "bidirectional"))
      (node (ref "R120") (pin "1") (pinfunction "A_1") (pintype "passive"))
    )
    (net (code "94") (name "Net-(PIC1-RD7{slash}PSP7{slash}P1D)") (class "Default")
      (node (ref "PIC1") (pin "5") (pinfunction "RD7/PSP7/P1D_5") (pintype "bidirectional"))
      (node (ref "R121") (pin "1") (pinfunction "A_1") (pintype "passive"))
    )
    (net (code "95") (name "Net-(PIC1-RE1{slash}~{WR{slash}AN6{slash}C1OUT})") (class "Default")
      (node (ref "PIC1") (pin "26") (pinfunction "RE1/~{WR/AN6/C1OUT}_26") (pintype "bidirectional"))
      (node (ref "R106") (pin "1") (pinfunction "A_1") (pintype "passive"))
    )
    (net (code "96") (name "Net-(PIC1-RE2{slash}~{CS{slash}AN7{slash}C2OUT})") (class "Default")
      (node (ref "PIC1") (pin "27") (pinfunction "RE2/~{CS/AN7/C2OUT}_27") (pintype "bidirectional"))
      (node (ref "R105") (pin "1") (pinfunction "A_1") (pintype "passive"))
    )
    (net (code "97") (name "Net-(PIC1-VDDCORE{slash}VCAP)") (class "Default")
      (node (ref "C3") (pin "1") (pinfunction "1_1") (pintype "passive"))
      (node (ref "PIC1") (pin "23") (pinfunction "VDDCORE/VCAP_23") (pintype "bidirectional"))
    )
    (net (code "98") (name "Net-(PIC1-~{MCLR{slash}VPP{slash}RE3})") (class "Default")
      (node (ref "CN_TANIT") (pin "3") (pinfunction "3_3") (pintype "passive"))
      (node (ref "PIC1") (pin "18") (pinfunction "~{MCLR/VPP/RE3}_18") (pintype "input"))
      (node (ref "R1") (pin "1") (pinfunction "A_1") (pintype "passive"))
    )
    (net (code "99") (name "Net-(R29-A)") (class "Default")
      (node (ref "R29") (pin "1") (pinfunction "A_1") (pintype "passive"))
      (node (ref "R53") (pin "2") (pinfunction "E_2") (pintype "passive"))
      (node (ref "R77") (pin "2") (pinfunction "E_2") (pintype "passive"))
      (node (ref "ZOLD_3P1") (pin "2") (pinfunction "1_2") (pintype "passive"))
    )
    (net (code "100") (name "Net-(R29-E)") (class "Default")
      (node (ref "R29") (pin "2") (pinfunction "E_2") (pintype "passive"))
      (node (ref "U5") (pin "P$6") (pinfunction "D_P$6") (pintype "passive"))
    )
    (net (code "101") (name "Net-(R30-A)") (class "Default")
      (node (ref "R30") (pin "1") (pinfunction "A_1") (pintype "passive"))
      (node (ref "R54") (pin "2") (pinfunction "E_2") (pintype "passive"))
      (node (ref "R78") (pin "2") (pinfunction "E_2") (pintype "passive"))
      (node (ref "ZOLD_3P1") (pin "3") (pinfunction "1_3") (pintype "passive"))
    )
    (net (code "102") (name "Net-(R30-E)") (class "Default")
      (node (ref "R30") (pin "2") (pinfunction "E_2") (pintype "passive"))
      (node (ref "U5") (pin "P$4") (pinfunction "D_P$4") (pintype "passive"))
    )
    (net (code "103") (name "Net-(R31-A)") (class "Default")
      (node (ref "R31") (pin "1") (pinfunction "A_1") (pintype "passive"))
      (node (ref "R55") (pin "2") (pinfunction "E_2") (pintype "passive"))
      (node (ref "R79") (pin "2") (pinfunction "E_2") (pintype "passive"))
      (node (ref "ZOLD_3P2") (pin "2") (pinfunction "1_2") (pintype "passive"))
    )
    (net (code "104") (name "Net-(R31-E)") (class "Default")
      (node (ref "R31") (pin "2") (pinfunction "E_2") (pintype "passive"))
      (node (ref "U6") (pin "P$6") (pinfunction "D_P$6") (pintype "passive"))
    )
    (net (code "105") (name "Net-(R32-A)") (class "Default")
      (node (ref "R32") (pin "1") (pinfunction "A_1") (pintype "passive"))
      (node (ref "R56") (pin "2") (pinfunction "E_2") (pintype "passive"))
      (node (ref "R80") (pin "2") (pinfunction "E_2") (pintype "passive"))
      (node (ref "ZOLD_3P2") (pin "3") (pinfunction "1_3") (pintype "passive"))
    )
    (net (code "106") (name "Net-(R32-E)") (class "Default")
      (node (ref "R32") (pin "2") (pinfunction "E_2") (pintype "passive"))
      (node (ref "U6") (pin "P$4") (pinfunction "D_P$4") (pintype "passive"))
    )
    (net (code "107") (name "Net-(R33-A)") (class "Default")
      (node (ref "R33") (pin "1") (pinfunction "A_1") (pintype "passive"))
      (node (ref "R57") (pin "2") (pinfunction "E_2") (pintype "passive"))
      (node (ref "R81") (pin "2") (pinfunction "E_2") (pintype "passive"))
      (node (ref "ZOLD_3P3") (pin "2") (pinfunction "1_2") (pintype "passive"))
    )
    (net (code "108") (name "Net-(R33-E)") (class "Default")
      (node (ref "R33") (pin "2") (pinfunction "E_2") (pintype "passive"))
      (node (ref "U7") (pin "P$6") (pinfunction "D_P$6") (pintype "passive"))
    )
    (net (code "109") (name "Net-(R34-A)") (class "Default")
      (node (ref "R34") (pin "1") (pinfunction "A_1") (pintype "passive"))
      (node (ref "R58") (pin "2") (pinfunction "E_2") (pintype "passive"))
      (node (ref "R82") (pin "2") (pinfunction "E_2") (pintype "passive"))
      (node (ref "ZOLD_3P3") (pin "3") (pinfunction "1_3") (pintype "passive"))
    )
    (net (code "110") (name "Net-(R34-E)") (class "Default")
      (node (ref "R34") (pin "2") (pinfunction "E_2") (pintype "passive"))
      (node (ref "U7") (pin "P$4") (pinfunction "D_P$4") (pintype "passive"))
    )
    (net (code "111") (name "Net-(R35-A)") (class "Default")
      (node (ref "R35") (pin "1") (pinfunction "A_1") (pintype "passive"))
      (node (ref "R59") (pin "2") (pinfunction "E_2") (pintype "passive"))
      (node (ref "R83") (pin "2") (pinfunction "E_2") (pintype "passive"))
      (node (ref "ZOLD_3P4") (pin "2") (pinfunction "1_2") (pintype "passive"))
    )
    (net (code "112") (name "Net-(R35-E)") (class "Default")
      (node (ref "R35") (pin "2") (pinfunction "E_2") (pintype "passive"))
      (node (ref "U8") (pin "P$6") (pinfunction "D_P$6") (pintype "passive"))
    )
    (net (code "113") (name "Net-(R36-A)") (class "Default")
      (node (ref "R36") (pin "1") (pinfunction "A_1") (pintype "passive"))
      (node (ref "R60") (pin "2") (pinfunction "E_2") (pintype "passive"))
      (node (ref "R84") (pin "2") (pinfunction "E_2") (pintype "passive"))
      (node (ref "ZOLD_3P4") (pin "3") (pinfunction "1_3") (pintype "passive"))
    )
    (net (code "114") (name "Net-(R36-E)") (class "Default")
      (node (ref "R36") (pin "2") (pinfunction "E_2") (pintype "passive"))
      (node (ref "U8") (pin "P$4") (pinfunction "D_P$4") (pintype "passive"))
    )
    (net (code "115") (name "Net-(R37-A)") (class "Default")
      (node (ref "R37") (pin "1") (pinfunction "A_1") (pintype "passive"))
      (node (ref "R61") (pin "2") (pinfunction "E_2") (pintype "passive"))
      (node (ref "R85") (pin "2") (pinfunction "E_2") (pintype "passive"))
      (node (ref "ZOLD_3P5") (pin "2") (pinfunction "1_2") (pintype "passive"))
    )
    (net (code "116") (name "Net-(R37-E)") (class "Default")
      (node (ref "R37") (pin "2") (pinfunction "E_2") (pintype "passive"))
      (node (ref "U9") (pin "P$6") (pinfunction "D_P$6") (pintype "passive"))
    )
    (net (code "117") (name "Net-(R38-A)") (class "Default")
      (node (ref "R38") (pin "1") (pinfunction "A_1") (pintype "passive"))
      (node (ref "R62") (pin "2") (pinfunction "E_2") (pintype "passive"))
      (node (ref "R86") (pin "2") (pinfunction "E_2") (pintype "passive"))
      (node (ref "ZOLD_3P5") (pin "3") (pinfunction "1_3") (pintype "passive"))
    )
    (net (code "118") (name "Net-(R38-E)") (class "Default")
      (node (ref "R38") (pin "2") (pinfunction "E_2") (pintype "passive"))
      (node (ref "U9") (pin "P$4") (pinfunction "D_P$4") (pintype "passive"))
    )
    (net (code "119") (name "Net-(R39-A)") (class "Default")
      (node (ref "R39") (pin "1") (pinfunction "A_1") (pintype "passive"))
      (node (ref "R63") (pin "2") (pinfunction "E_2") (pintype "passive"))
      (node (ref "R87") (pin "2") (pinfunction "E_2") (pintype "passive"))
      (node (ref "ZOLD_3P6") (pin "2") (pinfunction "1_2") (pintype "passive"))
    )
    (net (code "120") (name "Net-(R39-E)") (class "Default")
      (node (ref "R39") (pin "2") (pinfunction "E_2") (pintype "passive"))
      (node (ref "U10") (pin "P$6") (pinfunction "D_P$6") (pintype "passive"))
    )
    (net (code "121") (name "Net-(R40-A)") (class "Default")
      (node (ref "R40") (pin "1") (pinfunction "A_1") (pintype "passive"))
      (node (ref "R64") (pin "2") (pinfunction "E_2") (pintype "passive"))
      (node (ref "R88") (pin "2") (pinfunction "E_2") (pintype "passive"))
      (node (ref "ZOLD_3P6") (pin "3") (pinfunction "1_3") (pintype "passive"))
    )
    (net (code "122") (name "Net-(R40-E)") (class "Default")
      (node (ref "R40") (pin "2") (pinfunction "E_2") (pintype "passive"))
      (node (ref "U10") (pin "P$4") (pinfunction "D_P$4") (pintype "passive"))
    )
    (net (code "123") (name "Net-(R41-A)") (class "Default")
      (node (ref "R41") (pin "1") (pinfunction "A_1") (pintype "passive"))
      (node (ref "R65") (pin "2") (pinfunction "E_2") (pintype "passive"))
      (node (ref "R89") (pin "2") (pinfunction "E_2") (pintype "passive"))
      (node (ref "ZOLD_3P7") (pin "2") (pinfunction "1_2") (pintype "passive"))
    )
    (net (code "124") (name "Net-(R41-E)") (class "Default")
      (node (ref "R41") (pin "2") (pinfunction "E_2") (pintype "passive"))
      (node (ref "U11") (pin "P$6") (pinfunction "D_P$6") (pintype "passive"))
    )
    (net (code "125") (name "Net-(R42-A)") (class "Default")
      (node (ref "R42") (pin "1") (pinfunction "A_1") (pintype "passive"))
      (node (ref "R66") (pin "2") (pinfunction "E_2") (pintype "passive"))
      (node (ref "R90") (pin "2") (pinfunction "E_2") (pintype "passive"))
      (node (ref "ZOLD_3P7") (pin "3") (pinfunction "1_3") (pintype "passive"))
    )
    (net (code "126") (name "Net-(R42-E)") (class "Default")
      (node (ref "R42") (pin "2") (pinfunction "E_2") (pintype "passive"))
      (node (ref "U11") (pin "P$4") (pinfunction "D_P$4") (pintype "passive"))
    )
    (net (code "127") (name "Net-(R43-A)") (class "Default")
      (node (ref "R43") (pin "1") (pinfunction "A_1") (pintype "passive"))
      (node (ref "R67") (pin "2") (pinfunction "E_2") (pintype "passive"))
      (node (ref "R91") (pin "2") (pinfunction "E_2") (pintype "passive"))
      (node (ref "ZOLD_3P8") (pin "2") (pinfunction "1_2") (pintype "passive"))
    )
    (net (code "128") (name "Net-(R43-E)") (class "Default")
      (node (ref "R43") (pin "2") (pinfunction "E_2") (pintype "passive"))
      (node (ref "U12") (pin "P$6") (pinfunction "D_P$6") (pintype "passive"))
    )
    (net (code "129") (name "Net-(R44-A)") (class "Default")
      (node (ref "R44") (pin "1") (pinfunction "A_1") (pintype "passive"))
      (node (ref "R68") (pin "2") (pinfunction "E_2") (pintype "passive"))
      (node (ref "R92") (pin "2") (pinfunction "E_2") (pintype "passive"))
      (node (ref "ZOLD_3P8") (pin "3") (pinfunction "1_3") (pintype "passive"))
    )
    (net (code "130") (name "Net-(R44-E)") (class "Default")
      (node (ref "R44") (pin "2") (pinfunction "E_2") (pintype "passive"))
      (node (ref "U12") (pin "P$4") (pinfunction "D_P$4") (pintype "passive"))
    )
    (net (code "131") (name "Net-(R45-A)") (class "Default")
      (node (ref "R45") (pin "1") (pinfunction "A_1") (pintype "passive"))
      (node (ref "R69") (pin "2") (pinfunction "E_2") (pintype "passive"))
      (node (ref "R93") (pin "2") (pinfunction "E_2") (pintype "passive"))
      (node (ref "ZOLD_3P9") (pin "2") (pinfunction "1_2") (pintype "passive"))
    )
    (net (code "132") (name "Net-(R45-E)") (class "Default")
      (node (ref "R45") (pin "2") (pinfunction "E_2") (pintype "passive"))
      (node (ref "U13") (pin "P$6") (pinfunction "D_P$6") (pintype "passive"))
    )
    (net (code "133") (name "Net-(R46-A)") (class "Default")
      (node (ref "R46") (pin "1") (pinfunction "A_1") (pintype "passive"))
      (node (ref "R70") (pin "2") (pinfunction "E_2") (pintype "passive"))
      (node (ref "R94") (pin "2") (pinfunction "E_2") (pintype "passive"))
      (node (ref "ZOLD_3P9") (pin "3") (pinfunction "1_3") (pintype "passive"))
    )
    (net (code "134") (name "Net-(R46-E)") (class "Default")
      (node (ref "R46") (pin "2") (pinfunction "E_2") (pintype "passive"))
      (node (ref "U13") (pin "P$4") (pinfunction "D_P$4") (pintype "passive"))
    )
    (net (code "135") (name "Net-(R47-A)") (class "Default")
      (node (ref "R47") (pin "1") (pinfunction "A_1") (pintype "passive"))
      (node (ref "R71") (pin "2") (pinfunction "E_2") (pintype "passive"))
      (node (ref "R95") (pin "2") (pinfunction "E_2") (pintype "passive"))
      (node (ref "ZOLD_3P10") (pin "2") (pinfunction "1_2") (pintype "passive"))
    )
    (net (code "136") (name "Net-(R47-E)") (class "Default")
      (node (ref "R47") (pin "2") (pinfunction "E_2") (pintype "passive"))
      (node (ref "U14") (pin "P$6") (pinfunction "D_P$6") (pintype "passive"))
    )
    (net (code "137") (name "Net-(R48-A)") (class "Default")
      (node (ref "R48") (pin "1") (pinfunction "A_1") (pintype "passive"))
      (node (ref "R72") (pin "2") (pinfunction "E_2") (pintype "passive"))
      (node (ref "R96") (pin "2") (pinfunction "E_2") (pintype "passive"))
      (node (ref "ZOLD_3P10") (pin "3") (pinfunction "1_3") (pintype "passive"))
    )
    (net (code "138") (name "Net-(R48-E)") (class "Default")
      (node (ref "R48") (pin "2") (pinfunction "E_2") (pintype "passive"))
      (node (ref "U14") (pin "P$4") (pinfunction "D_P$4") (pintype "passive"))
    )
    (net (code "139") (name "Net-(R49-A)") (class "Default")
      (node (ref "R49") (pin "1") (pinfunction "A_1") (pintype "passive"))
      (node (ref "R73") (pin "2") (pinfunction "E_2") (pintype "passive"))
      (node (ref "R97") (pin "2") (pinfunction "E_2") (pintype "passive"))
      (node (ref "ZOLD_3P11") (pin "2") (pinfunction "1_2") (pintype "passive"))
    )
    (net (code "140") (name "Net-(R49-E)") (class "Default")
      (node (ref "R49") (pin "2") (pinfunction "E_2") (pintype "passive"))
      (node (ref "U15") (pin "P$6") (pinfunction "D_P$6") (pintype "passive"))
    )
    (net (code "141") (name "Net-(R50-A)") (class "Default")
      (node (ref "R50") (pin "1") (pinfunction "A_1") (pintype "passive"))
      (node (ref "R74") (pin "2") (pinfunction "E_2") (pintype "passive"))
      (node (ref "R98") (pin "2") (pinfunction "E_2") (pintype "passive"))
      (node (ref "ZOLD_3P11") (pin "3") (pinfunction "1_3") (pintype "passive"))
    )
    (net (code "142") (name "Net-(R50-E)") (class "Default")
      (node (ref "R50") (pin "2") (pinfunction "E_2") (pintype "passive"))
      (node (ref "U15") (pin "P$4") (pinfunction "D_P$4") (pintype "passive"))
    )
    (net (code "143") (name "Net-(R51-A)") (class "Default")
      (node (ref "R51") (pin "1") (pinfunction "A_1") (pintype "passive"))
      (node (ref "R75") (pin "2") (pinfunction "E_2") (pintype "passive"))
      (node (ref "R99") (pin "2") (pinfunction "E_2") (pintype "passive"))
      (node (ref "ZOLD_3P12") (pin "2") (pinfunction "1_2") (pintype "passive"))
    )
    (net (code "144") (name "Net-(R51-E)") (class "Default")
      (node (ref "R51") (pin "2") (pinfunction "E_2") (pintype "passive"))
      (node (ref "U16") (pin "P$6") (pinfunction "D_P$6") (pintype "passive"))
    )
    (net (code "145") (name "Net-(R52-E)") (class "Default")
      (node (ref "R52") (pin "2") (pinfunction "E_2") (pintype "passive"))
      (node (ref "U16") (pin "P$4") (pinfunction "D_P$4") (pintype "passive"))
    )
    (net (code "146") (name "Net-(R100-E)") (class "Default")
      (node (ref "R100") (pin "2") (pinfunction "E_2") (pintype "passive"))
      (node (ref "R52") (pin "1") (pinfunction "A_1") (pintype "passive"))
      (node (ref "R76") (pin "2") (pinfunction "E_2") (pintype "passive"))
      (node (ref "ZOLD_3P12") (pin "3") (pinfunction "1_3") (pintype "passive"))
    )
    (net (code "147") (name "Net-(R125-E)") (class "Default")
      (node (ref "CN_CANLEZAR") (pin "1") (pinfunction "1_1") (pintype "passive"))
      (node (ref "R125") (pin "2") (pinfunction "E_2") (pintype "passive"))
    )
    (net (code "148") (name "Net-(R126-A)") (class "Default")
      (node (ref "CN_CANLEZAR") (pin "3") (pinfunction "3_3") (pintype "passive"))
      (node (ref "R126") (pin "1") (pinfunction "A_1") (pintype "passive"))
    )
    (net (code "149") (name "unconnected-(CANIC-VREF-Pad5)") (class "Default")
      (node (ref "CANIC") (pin "5") (pinfunction "VREF_5") (pintype "output"))
    )
    (net (code "150") (name "unconnected-(CN_RJ1-Pad1)") (class "Default")
      (node (ref "CN_RJ1") (pin "1") (pinfunction "1_1") (pintype "passive"))
    )
    (net (code "151") (name "unconnected-(CN_RJ1-Pad2)") (class "Default")
      (node (ref "CN_RJ1") (pin "2") (pinfunction "2_2") (pintype "passive"))
    )
    (net (code "152") (name "unconnected-(CN_RJ1-Pad3)") (class "Default")
      (node (ref "CN_RJ1") (pin "3") (pinfunction "3_3") (pintype "passive"))
    )
    (net (code "153") (name "unconnected-(CN_RJ1-Pad6)") (class "Default")
      (node (ref "CN_RJ1") (pin "6") (pinfunction "6_6") (pintype "passive"))
    )
    (net (code "154") (name "unconnected-(CN_RJ2-Pad1)") (class "Default")
      (node (ref "CN_RJ2") (pin "1") (pinfunction "1_1") (pintype "passive"))
    )
    (net (code "155") (name "unconnected-(CN_RJ2-Pad2)") (class "Default")
      (node (ref "CN_RJ2") (pin "2") (pinfunction "2_2") (pintype "passive"))
    )
    (net (code "156") (name "unconnected-(CN_RJ2-Pad3)") (class "Default")
      (node (ref "CN_RJ2") (pin "3") (pinfunction "3_3") (pintype "passive"))
    )
    (net (code "157") (name "unconnected-(CN_RJ2-Pad6)") (class "Default")
      (node (ref "CN_RJ2") (pin "6") (pinfunction "6_6") (pintype "passive"))
    )
    (net (code "158") (name "unconnected-(IC9-14_SDO-Pad14)") (class "Default")
      (node (ref "IC9") (pin "14") (pinfunction "14_SDO_14") (pintype "output"))
    )
    (net (code "159") (name "unconnected-(PIC1-NC-Pad34)") (class "Default")
      (node (ref "PIC1") (pin "34") (pinfunction "NC_34") (pintype "no_connect"))
    )
    (net (code "160") (name "unconnected-(PIC1-NC_2-Pad12)") (class "Default")
      (node (ref "PIC1") (pin "12") (pinfunction "NC_2_12") (pintype "no_connect"))
    )
    (net (code "161") (name "unconnected-(PIC1-NC_3-Pad13)") (class "Default")
      (node (ref "PIC1") (pin "13") (pinfunction "NC_3_13") (pintype "no_connect"))
    )
    (net (code "162") (name "unconnected-(PIC1-NC_4-Pad33)") (class "Default")
      (node (ref "PIC1") (pin "33") (pinfunction "NC_4_33") (pintype "no_connect"))
    )
    (net (code "163") (name "unconnected-(PIC1-RE0{slash}~{RD{slash}AN5}-Pad25)") (class "Default")
      (node (ref "PIC1") (pin "25") (pinfunction "RE0/~{RD/AN5}_25") (pintype "bidirectional"))
    )
    (net (code "164") (name "unconnected-(U$20-PadP$2)") (class "Default")
      (node (ref "U$20") (pin "P$2") (pinfunction "P$2_P$2") (pintype "bidirectional"))
    )
  )
)
